# 12_-_CPU_-_POWER.net
KiCad netlist of a schematic drawn in Altium Designer
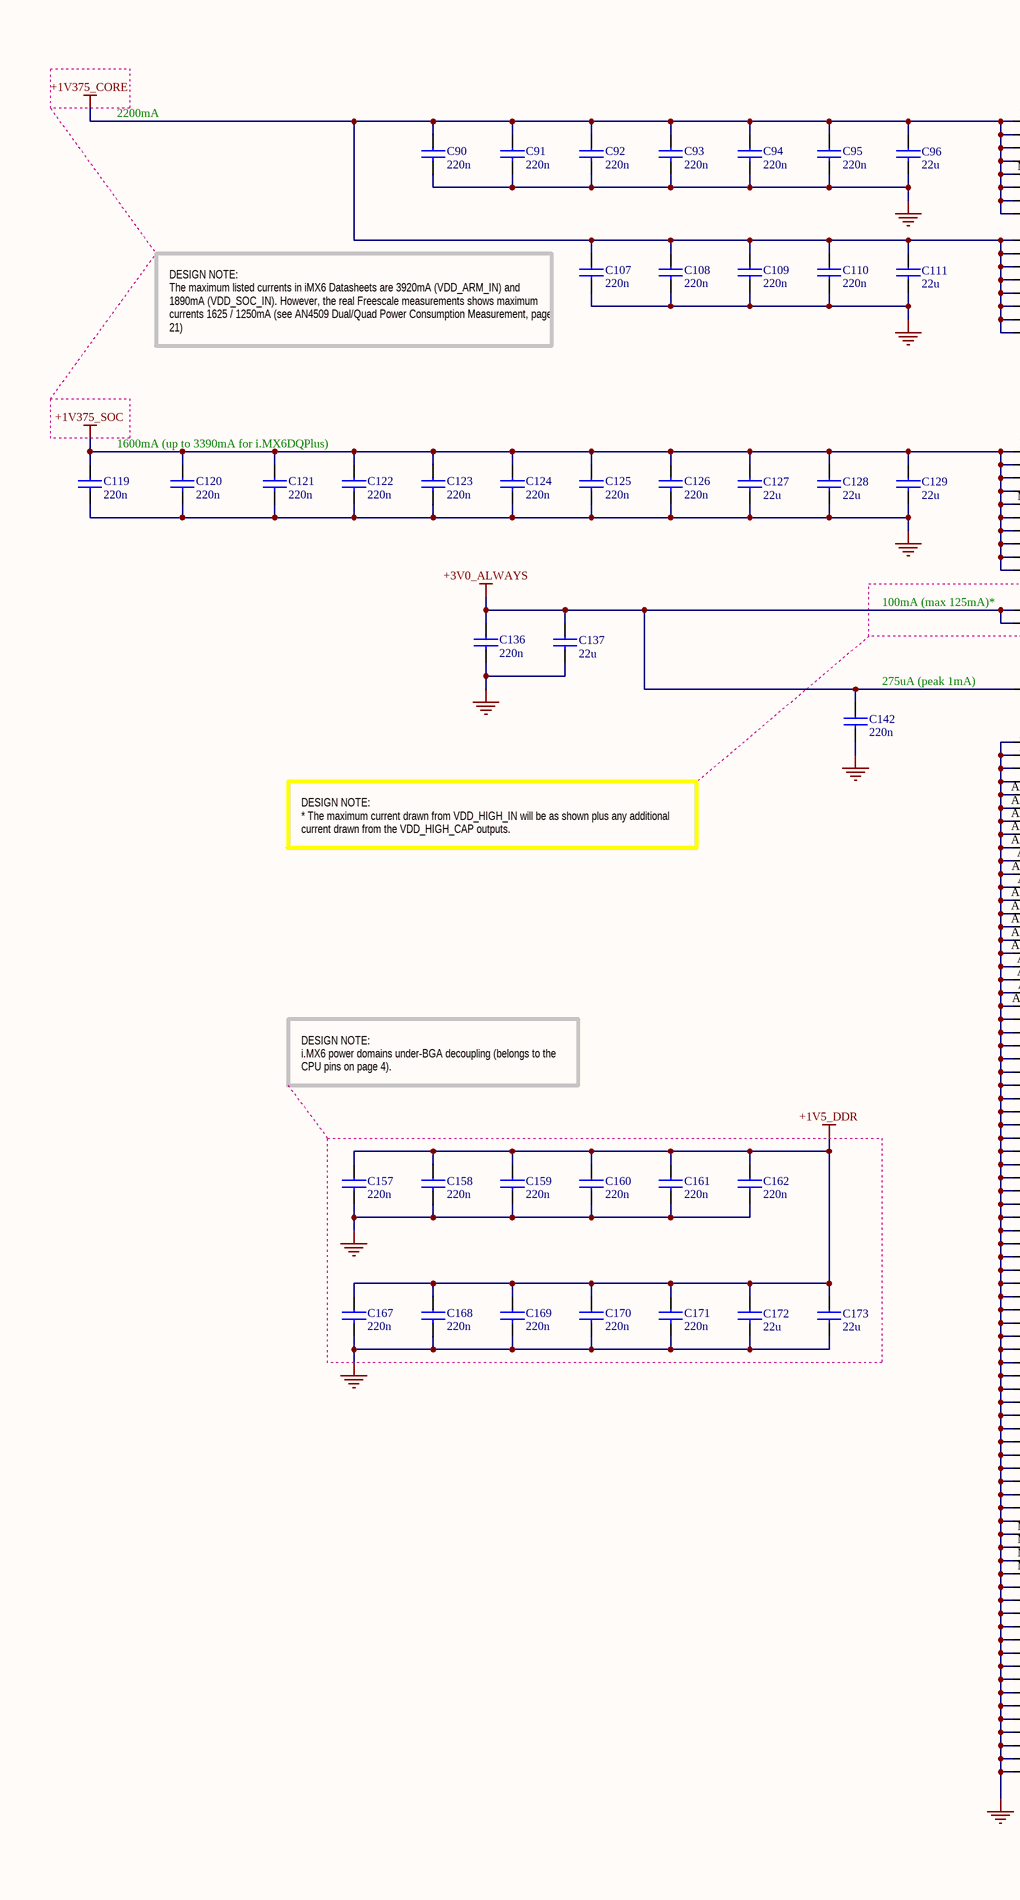
[diagram p0: [12] - CPU - POWER.SchDoc, left]
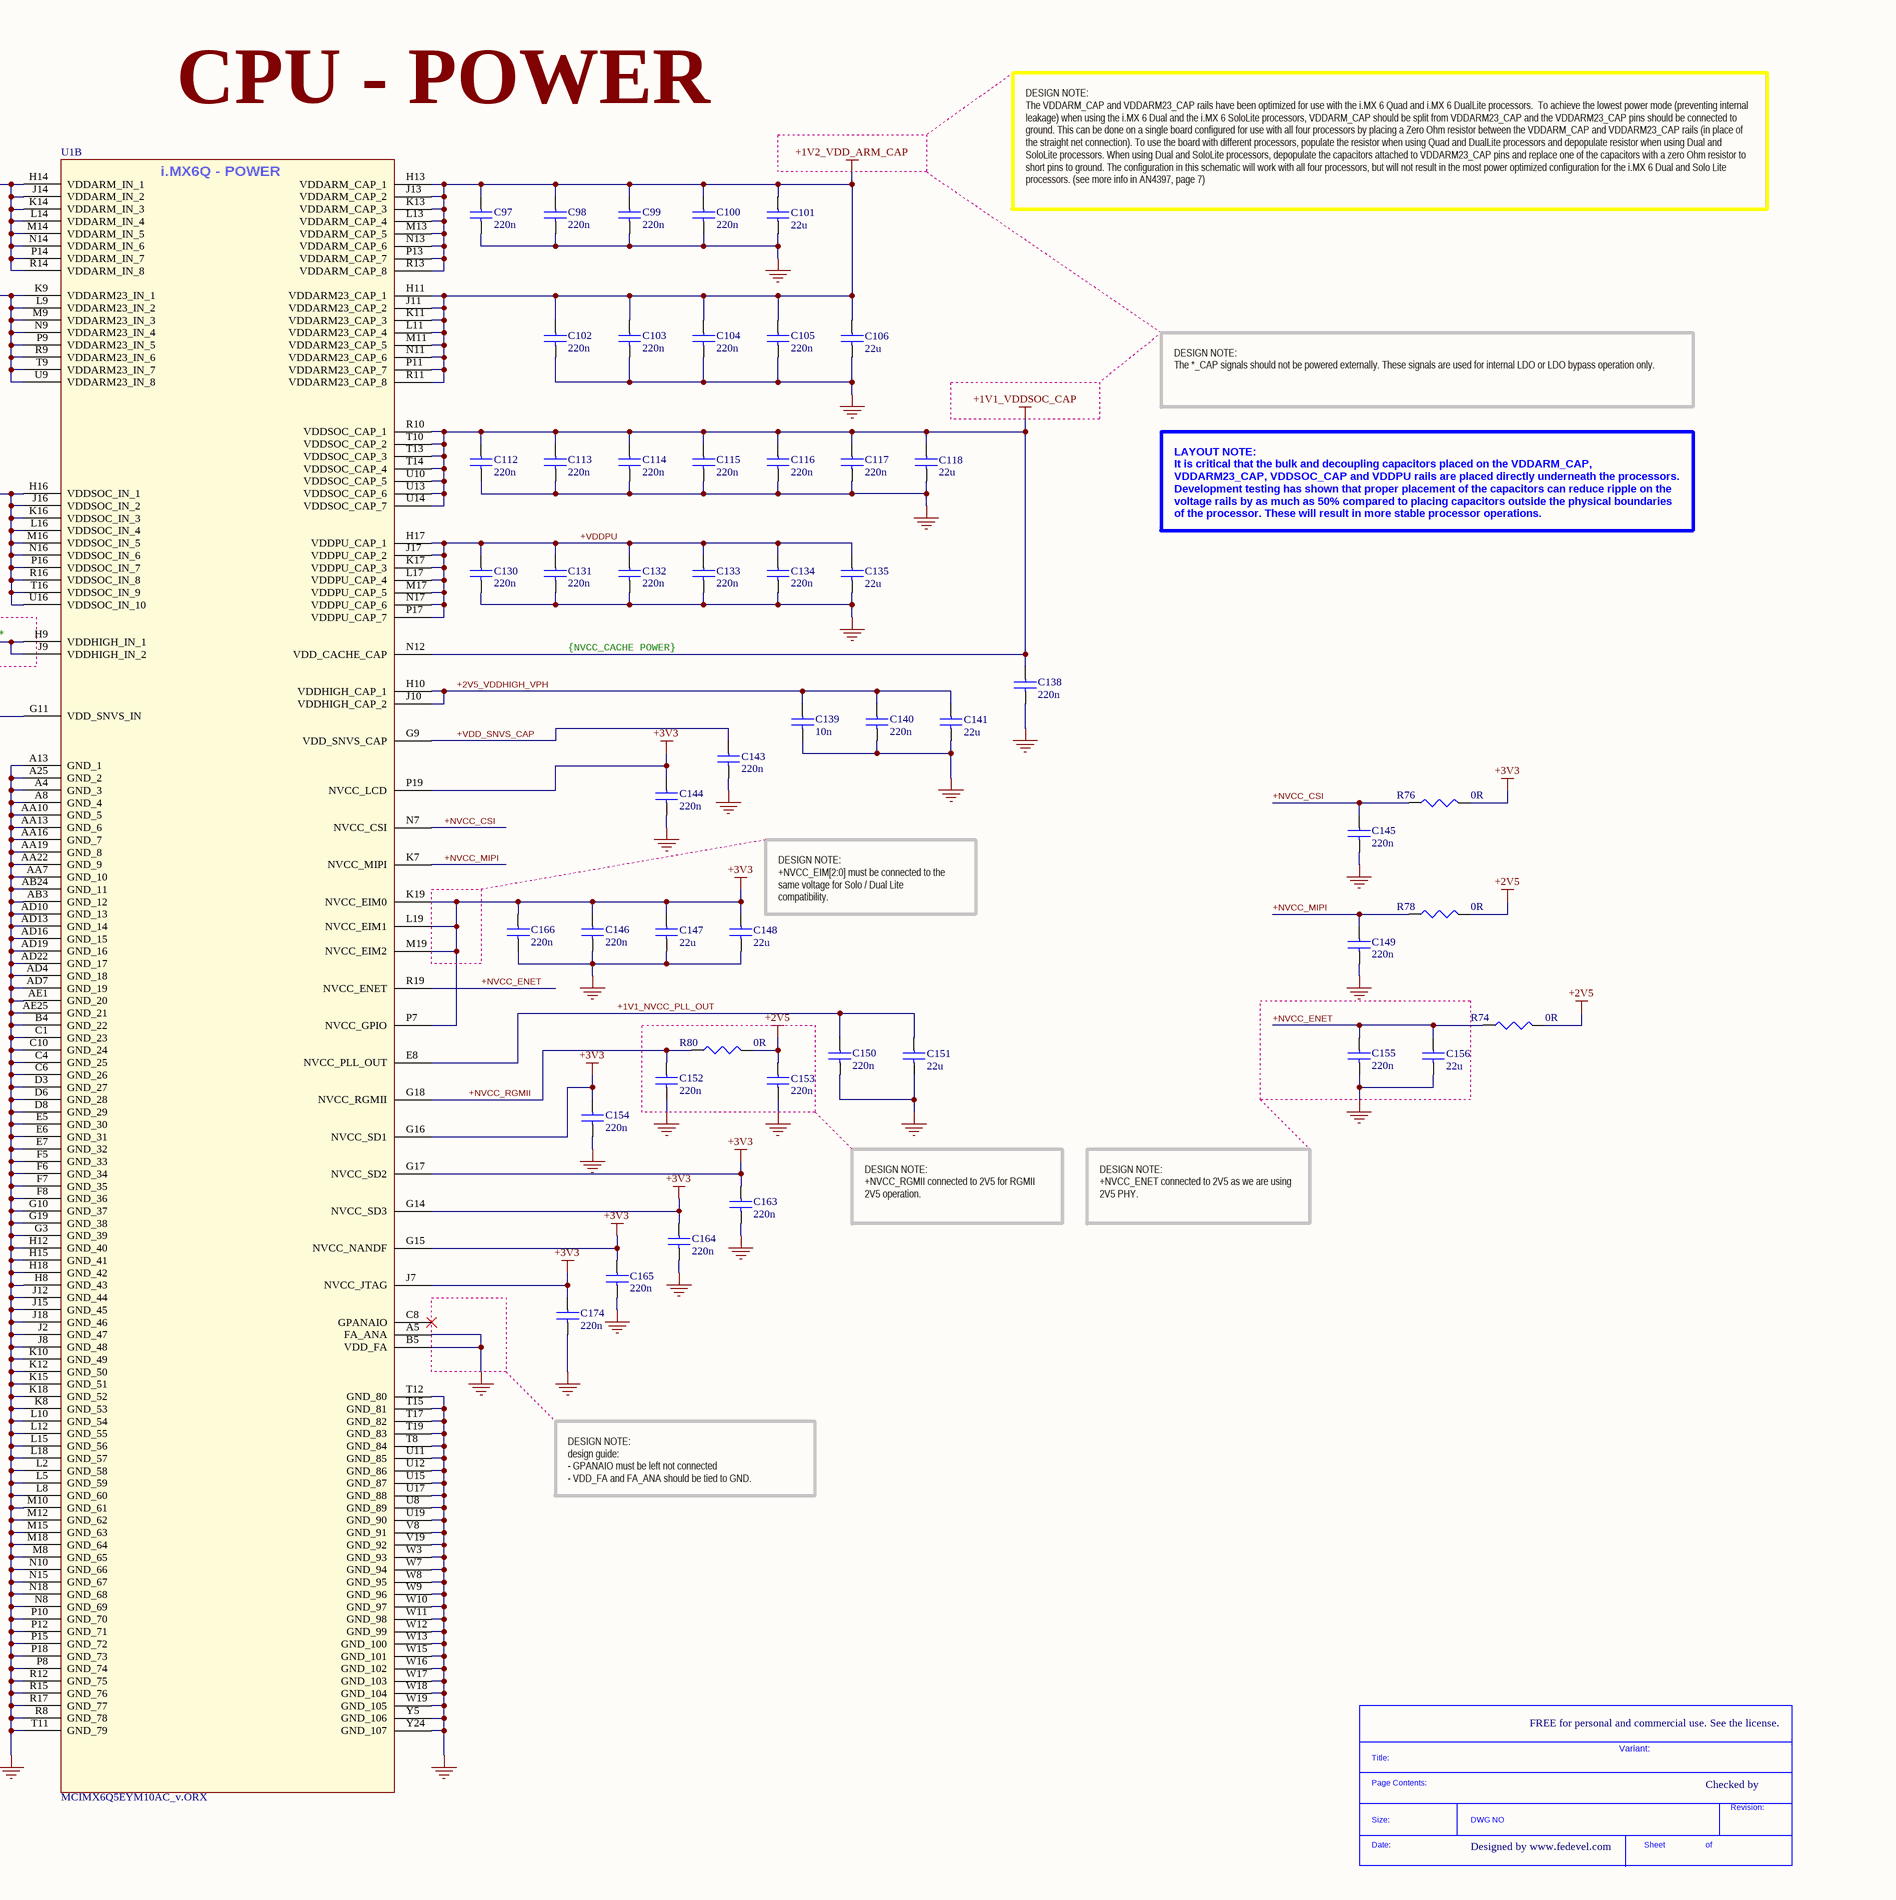
[diagram p1: [12] - CPU - POWER.SchDoc, right]

(export (version "E")
  (design (tool "Eeschema 10.0.6"))
  (components
    (comp (ref "C90")
      (value "220n")
      (footprint "C0201")
      (description "CAP CER 0.22UF 6.3V 20% X5R 0201")
      (fields
        (field (name "MANUFACTURER") "TDK Corporation")
        (field (name "MANUFACTURER PART NUMBER") "C0603X5R0J224M030BB")
        (field (name ".CHECKED PCB") "MM")
        (field (name ".CHECKED SCH") "MM")
        (field (name ".CREATOR") "MM")
      )
      (libsource (lib "Integrated_Library_FEDEVEL_0201") (part "C0603X5R0J224M030BB"))
    )
    (comp (ref "C91")
      (value "220n")
      (footprint "C0201")
      (description "CAP CER 0.22UF 6.3V 20% X5R 0201")
      (fields
        (field (name "MANUFACTURER") "TDK Corporation")
        (field (name "MANUFACTURER PART NUMBER") "C0603X5R0J224M030BB")
        (field (name ".CHECKED PCB") "MM")
        (field (name ".CHECKED SCH") "MM")
        (field (name ".CREATOR") "MM")
      )
      (libsource (lib "Integrated_Library_FEDEVEL_0201") (part "C0603X5R0J224M030BB"))
    )
    (comp (ref "C92")
      (value "220n")
      (footprint "C0201")
      (description "CAP CER 0.22UF 6.3V 20% X5R 0201")
      (fields
        (field (name "MANUFACTURER") "TDK Corporation")
        (field (name "MANUFACTURER PART NUMBER") "C0603X5R0J224M030BB")
        (field (name ".CHECKED PCB") "MM")
        (field (name ".CHECKED SCH") "MM")
        (field (name ".CREATOR") "MM")
      )
      (libsource (lib "Integrated_Library_FEDEVEL_0201") (part "C0603X5R0J224M030BB"))
    )
    (comp (ref "C93")
      (value "220n")
      (footprint "C0201")
      (description "CAP CER 0.22UF 6.3V 20% X5R 0201")
      (fields
        (field (name "MANUFACTURER") "TDK Corporation")
        (field (name "MANUFACTURER PART NUMBER") "C0603X5R0J224M030BB")
        (field (name ".CHECKED PCB") "MM")
        (field (name ".CHECKED SCH") "MM")
        (field (name ".CREATOR") "MM")
      )
      (libsource (lib "Integrated_Library_FEDEVEL_0201") (part "C0603X5R0J224M030BB"))
    )
    (comp (ref "C94")
      (value "220n")
      (footprint "C0201")
      (description "CAP CER 0.22UF 6.3V 20% X5R 0201")
      (fields
        (field (name "MANUFACTURER") "TDK Corporation")
        (field (name "MANUFACTURER PART NUMBER") "C0603X5R0J224M030BB")
        (field (name ".CHECKED PCB") "MM")
        (field (name ".CHECKED SCH") "MM")
        (field (name ".CREATOR") "MM")
      )
      (libsource (lib "Integrated_Library_FEDEVEL_0201") (part "C0603X5R0J224M030BB"))
    )
    (comp (ref "C95")
      (value "220n")
      (footprint "C0201")
      (description "CAP CER 0.22UF 6.3V 20% X5R 0201")
      (fields
        (field (name "MANUFACTURER") "TDK Corporation")
        (field (name "MANUFACTURER PART NUMBER") "C0603X5R0J224M030BB")
        (field (name ".CHECKED PCB") "MM")
        (field (name ".CHECKED SCH") "MM")
        (field (name ".CREATOR") "MM")
      )
      (libsource (lib "Integrated_Library_FEDEVEL_0201") (part "C0603X5R0J224M030BB"))
    )
    (comp (ref "C96")
      (value "22u")
      (footprint "C0603_small")
      (description "CAP CER 22UF 4V 20% X5R 0603")
      (fields
        (field (name "MANUFACTURER") "Murata Electronics North America")
        (field (name "MANUFACTURER PART NUMBER") "GRM188R60G226MEA0L")
        (field (name ".CHECKED PCB") "MM")
        (field (name ".CHECKED SCH") "RF, used by MM")
        (field (name ".CREATOR") "MM")
      )
      (libsource (lib "Integrated_Library_FEDEVEL_0201") (part "GRM188R60G226MEA0L_small"))
    )
    (comp (ref "C97")
      (value "220n")
      (footprint "C0201")
      (description "CAP CER 0.22UF 6.3V 20% X5R 0201")
      (fields
        (field (name "MANUFACTURER") "TDK Corporation")
        (field (name "MANUFACTURER PART NUMBER") "C0603X5R0J224M030BB")
        (field (name ".CHECKED PCB") "MM")
        (field (name ".CHECKED SCH") "MM")
        (field (name ".CREATOR") "MM")
      )
      (libsource (lib "Integrated_Library_FEDEVEL_0201") (part "C0603X5R0J224M030BB"))
    )
    (comp (ref "C98")
      (value "220n")
      (footprint "C0201")
      (description "CAP CER 0.22UF 6.3V 20% X5R 0201")
      (fields
        (field (name "MANUFACTURER") "TDK Corporation")
        (field (name "MANUFACTURER PART NUMBER") "C0603X5R0J224M030BB")
        (field (name ".CHECKED PCB") "MM")
        (field (name ".CHECKED SCH") "MM")
        (field (name ".CREATOR") "MM")
      )
      (libsource (lib "Integrated_Library_FEDEVEL_0201") (part "C0603X5R0J224M030BB"))
    )
    (comp (ref "C99")
      (value "220n")
      (footprint "C0201")
      (description "CAP CER 0.22UF 6.3V 20% X5R 0201")
      (fields
        (field (name "MANUFACTURER") "TDK Corporation")
        (field (name "MANUFACTURER PART NUMBER") "C0603X5R0J224M030BB")
        (field (name ".CHECKED PCB") "MM")
        (field (name ".CHECKED SCH") "MM")
        (field (name ".CREATOR") "MM")
      )
      (libsource (lib "Integrated_Library_FEDEVEL_0201") (part "C0603X5R0J224M030BB"))
    )
    (comp (ref "C100")
      (value "220n")
      (footprint "C0201")
      (description "CAP CER 0.22UF 6.3V 20% X5R 0201")
      (fields
        (field (name "MANUFACTURER") "TDK Corporation")
        (field (name "MANUFACTURER PART NUMBER") "C0603X5R0J224M030BB")
        (field (name ".CHECKED PCB") "MM")
        (field (name ".CHECKED SCH") "MM")
        (field (name ".CREATOR") "MM")
      )
      (libsource (lib "Integrated_Library_FEDEVEL_0201") (part "C0603X5R0J224M030BB"))
    )
    (comp (ref "C101")
      (value "22u")
      (footprint "C0603_small")
      (description "CAP CER 22UF 4V 20% X5R 0603")
      (fields
        (field (name "MANUFACTURER") "Murata Electronics North America")
        (field (name "MANUFACTURER PART NUMBER") "GRM188R60G226MEA0L")
        (field (name ".CHECKED PCB") "MM")
        (field (name ".CHECKED SCH") "RF, used by MM")
        (field (name ".CREATOR") "MM")
      )
      (libsource (lib "Integrated_Library_FEDEVEL_0201") (part "GRM188R60G226MEA0L_small"))
    )
    (comp (ref "C102")
      (value "220n")
      (footprint "C0201")
      (description "CAP CER 0.22UF 6.3V 20% X5R 0201")
      (fields
        (field (name "MANUFACTURER") "TDK Corporation")
        (field (name "MANUFACTURER PART NUMBER") "C0603X5R0J224M030BB")
        (field (name ".CHECKED PCB") "MM")
        (field (name ".CHECKED SCH") "MM")
        (field (name ".CREATOR") "MM")
      )
      (libsource (lib "Integrated_Library_FEDEVEL_0201") (part "C0603X5R0J224M030BB"))
    )
    (comp (ref "C103")
      (value "220n")
      (footprint "C0201")
      (description "CAP CER 0.22UF 6.3V 20% X5R 0201")
      (fields
        (field (name "MANUFACTURER") "TDK Corporation")
        (field (name "MANUFACTURER PART NUMBER") "C0603X5R0J224M030BB")
        (field (name ".CHECKED PCB") "MM")
        (field (name ".CHECKED SCH") "MM")
        (field (name ".CREATOR") "MM")
      )
      (libsource (lib "Integrated_Library_FEDEVEL_0201") (part "C0603X5R0J224M030BB"))
    )
    (comp (ref "C104")
      (value "220n")
      (footprint "C0201")
      (description "CAP CER 0.22UF 6.3V 20% X5R 0201")
      (fields
        (field (name "MANUFACTURER") "TDK Corporation")
        (field (name "MANUFACTURER PART NUMBER") "C0603X5R0J224M030BB")
        (field (name ".CHECKED PCB") "MM")
        (field (name ".CHECKED SCH") "MM")
        (field (name ".CREATOR") "MM")
      )
      (libsource (lib "Integrated_Library_FEDEVEL_0201") (part "C0603X5R0J224M030BB"))
    )
    (comp (ref "C105")
      (value "220n")
      (footprint "C0201")
      (description "CAP CER 0.22UF 6.3V 20% X5R 0201")
      (fields
        (field (name "MANUFACTURER") "TDK Corporation")
        (field (name "MANUFACTURER PART NUMBER") "C0603X5R0J224M030BB")
        (field (name ".CHECKED PCB") "MM")
        (field (name ".CHECKED SCH") "MM")
        (field (name ".CREATOR") "MM")
      )
      (libsource (lib "Integrated_Library_FEDEVEL_0201") (part "C0603X5R0J224M030BB"))
    )
    (comp (ref "C106")
      (value "22u")
      (footprint "C0603_small")
      (description "CAP CER 22UF 4V 20% X5R 0603")
      (fields
        (field (name "MANUFACTURER") "Murata Electronics North America")
        (field (name "MANUFACTURER PART NUMBER") "GRM188R60G226MEA0L")
        (field (name ".CHECKED PCB") "MM")
        (field (name ".CHECKED SCH") "RF, used by MM")
        (field (name ".CREATOR") "MM")
      )
      (libsource (lib "Integrated_Library_FEDEVEL_0201") (part "GRM188R60G226MEA0L_small"))
    )
    (comp (ref "C107")
      (value "220n")
      (footprint "C0201")
      (description "CAP CER 0.22UF 6.3V 20% X5R 0201")
      (fields
        (field (name "MANUFACTURER") "TDK Corporation")
        (field (name "MANUFACTURER PART NUMBER") "C0603X5R0J224M030BB")
        (field (name ".CHECKED PCB") "MM")
        (field (name ".CHECKED SCH") "MM")
        (field (name ".CREATOR") "MM")
      )
      (libsource (lib "Integrated_Library_FEDEVEL_0201") (part "C0603X5R0J224M030BB"))
    )
    (comp (ref "C108")
      (value "220n")
      (footprint "C0201")
      (description "CAP CER 0.22UF 6.3V 20% X5R 0201")
      (fields
        (field (name "MANUFACTURER") "TDK Corporation")
        (field (name "MANUFACTURER PART NUMBER") "C0603X5R0J224M030BB")
        (field (name ".CHECKED PCB") "MM")
        (field (name ".CHECKED SCH") "MM")
        (field (name ".CREATOR") "MM")
      )
      (libsource (lib "Integrated_Library_FEDEVEL_0201") (part "C0603X5R0J224M030BB"))
    )
    (comp (ref "C109")
      (value "220n")
      (footprint "C0201")
      (description "CAP CER 0.22UF 6.3V 20% X5R 0201")
      (fields
        (field (name "MANUFACTURER") "TDK Corporation")
        (field (name "MANUFACTURER PART NUMBER") "C0603X5R0J224M030BB")
        (field (name ".CHECKED PCB") "MM")
        (field (name ".CHECKED SCH") "MM")
        (field (name ".CREATOR") "MM")
      )
      (libsource (lib "Integrated_Library_FEDEVEL_0201") (part "C0603X5R0J224M030BB"))
    )
    (comp (ref "C110")
      (value "220n")
      (footprint "C0201")
      (description "CAP CER 0.22UF 6.3V 20% X5R 0201")
      (fields
        (field (name "MANUFACTURER") "TDK Corporation")
        (field (name "MANUFACTURER PART NUMBER") "C0603X5R0J224M030BB")
        (field (name ".CHECKED PCB") "MM")
        (field (name ".CHECKED SCH") "MM")
        (field (name ".CREATOR") "MM")
      )
      (libsource (lib "Integrated_Library_FEDEVEL_0201") (part "C0603X5R0J224M030BB"))
    )
    (comp (ref "C111")
      (value "22u")
      (footprint "C0603_small")
      (description "CAP CER 22UF 4V 20% X5R 0603")
      (fields
        (field (name "MANUFACTURER") "Murata Electronics North America")
        (field (name "MANUFACTURER PART NUMBER") "GRM188R60G226MEA0L")
        (field (name ".CHECKED PCB") "MM")
        (field (name ".CHECKED SCH") "RF, used by MM")
        (field (name ".CREATOR") "MM")
      )
      (libsource (lib "Integrated_Library_FEDEVEL_0201") (part "GRM188R60G226MEA0L_small"))
    )
    (comp (ref "C112")
      (value "220n")
      (footprint "C0201")
      (description "CAP CER 0.22UF 6.3V 20% X5R 0201")
      (fields
        (field (name "MANUFACTURER") "TDK Corporation")
        (field (name "MANUFACTURER PART NUMBER") "C0603X5R0J224M030BB")
        (field (name ".CHECKED PCB") "MM")
        (field (name ".CHECKED SCH") "MM")
        (field (name ".CREATOR") "MM")
      )
      (libsource (lib "Integrated_Library_FEDEVEL_0201") (part "C0603X5R0J224M030BB"))
    )
    (comp (ref "C113")
      (value "220n")
      (footprint "C0201")
      (description "CAP CER 0.22UF 6.3V 20% X5R 0201")
      (fields
        (field (name "MANUFACTURER") "TDK Corporation")
        (field (name "MANUFACTURER PART NUMBER") "C0603X5R0J224M030BB")
        (field (name ".CHECKED PCB") "MM")
        (field (name ".CHECKED SCH") "MM")
        (field (name ".CREATOR") "MM")
      )
      (libsource (lib "Integrated_Library_FEDEVEL_0201") (part "C0603X5R0J224M030BB"))
    )
    (comp (ref "C114")
      (value "220n")
      (footprint "C0201")
      (description "CAP CER 0.22UF 6.3V 20% X5R 0201")
      (fields
        (field (name "MANUFACTURER") "TDK Corporation")
        (field (name "MANUFACTURER PART NUMBER") "C0603X5R0J224M030BB")
        (field (name ".CHECKED PCB") "MM")
        (field (name ".CHECKED SCH") "MM")
        (field (name ".CREATOR") "MM")
      )
      (libsource (lib "Integrated_Library_FEDEVEL_0201") (part "C0603X5R0J224M030BB"))
    )
    (comp (ref "C115")
      (value "220n")
      (footprint "C0201")
      (description "CAP CER 0.22UF 6.3V 20% X5R 0201")
      (fields
        (field (name "MANUFACTURER") "TDK Corporation")
        (field (name "MANUFACTURER PART NUMBER") "C0603X5R0J224M030BB")
        (field (name ".CHECKED PCB") "MM")
        (field (name ".CHECKED SCH") "MM")
        (field (name ".CREATOR") "MM")
      )
      (libsource (lib "Integrated_Library_FEDEVEL_0201") (part "C0603X5R0J224M030BB"))
    )
    (comp (ref "C116")
      (value "220n")
      (footprint "C0201")
      (description "CAP CER 0.22UF 6.3V 20% X5R 0201")
      (fields
        (field (name "MANUFACTURER") "TDK Corporation")
        (field (name "MANUFACTURER PART NUMBER") "C0603X5R0J224M030BB")
        (field (name ".CHECKED PCB") "MM")
        (field (name ".CHECKED SCH") "MM")
        (field (name ".CREATOR") "MM")
      )
      (libsource (lib "Integrated_Library_FEDEVEL_0201") (part "C0603X5R0J224M030BB"))
    )
    (comp (ref "C117")
      (value "220n")
      (footprint "C0201")
      (description "CAP CER 0.22UF 6.3V 20% X5R 0201")
      (fields
        (field (name "MANUFACTURER") "TDK Corporation")
        (field (name "MANUFACTURER PART NUMBER") "C0603X5R0J224M030BB")
        (field (name ".CHECKED PCB") "MM")
        (field (name ".CHECKED SCH") "MM")
        (field (name ".CREATOR") "MM")
      )
      (libsource (lib "Integrated_Library_FEDEVEL_0201") (part "C0603X5R0J224M030BB"))
    )
    (comp (ref "C118")
      (value "22u")
      (footprint "C0603_small")
      (description "CAP CER 22UF 4V 20% X5R 0603")
      (fields
        (field (name "MANUFACTURER") "Murata Electronics North America")
        (field (name "MANUFACTURER PART NUMBER") "GRM188R60G226MEA0L")
        (field (name ".CHECKED PCB") "MM")
        (field (name ".CHECKED SCH") "RF, used by MM")
        (field (name ".CREATOR") "MM")
      )
      (libsource (lib "Integrated_Library_FEDEVEL_0201") (part "GRM188R60G226MEA0L_small"))
    )
    (comp (ref "C119")
      (value "220n")
      (footprint "C0201")
      (description "CAP CER 0.22UF 6.3V 20% X5R 0201")
      (fields
        (field (name "MANUFACTURER") "TDK Corporation")
        (field (name "MANUFACTURER PART NUMBER") "C0603X5R0J224M030BB")
        (field (name ".CHECKED PCB") "MM")
        (field (name ".CHECKED SCH") "MM")
        (field (name ".CREATOR") "MM")
      )
      (libsource (lib "Integrated_Library_FEDEVEL_0201") (part "C0603X5R0J224M030BB"))
    )
    (comp (ref "C120")
      (value "220n")
      (footprint "C0201")
      (description "CAP CER 0.22UF 6.3V 20% X5R 0201")
      (fields
        (field (name "MANUFACTURER") "TDK Corporation")
        (field (name "MANUFACTURER PART NUMBER") "C0603X5R0J224M030BB")
        (field (name ".CHECKED PCB") "MM")
        (field (name ".CHECKED SCH") "MM")
        (field (name ".CREATOR") "MM")
      )
      (libsource (lib "Integrated_Library_FEDEVEL_0201") (part "C0603X5R0J224M030BB"))
    )
    (comp (ref "C121")
      (value "220n")
      (footprint "C0201")
      (description "CAP CER 0.22UF 6.3V 20% X5R 0201")
      (fields
        (field (name "MANUFACTURER") "TDK Corporation")
        (field (name "MANUFACTURER PART NUMBER") "C0603X5R0J224M030BB")
        (field (name ".CHECKED PCB") "MM")
        (field (name ".CHECKED SCH") "MM")
        (field (name ".CREATOR") "MM")
      )
      (libsource (lib "Integrated_Library_FEDEVEL_0201") (part "C0603X5R0J224M030BB"))
    )
    (comp (ref "C122")
      (value "220n")
      (footprint "C0201")
      (description "CAP CER 0.22UF 6.3V 20% X5R 0201")
      (fields
        (field (name "MANUFACTURER") "TDK Corporation")
        (field (name "MANUFACTURER PART NUMBER") "C0603X5R0J224M030BB")
        (field (name ".CHECKED PCB") "MM")
        (field (name ".CHECKED SCH") "MM")
        (field (name ".CREATOR") "MM")
      )
      (libsource (lib "Integrated_Library_FEDEVEL_0201") (part "C0603X5R0J224M030BB"))
    )
    (comp (ref "C123")
      (value "220n")
      (footprint "C0201")
      (description "CAP CER 0.22UF 6.3V 20% X5R 0201")
      (fields
        (field (name "MANUFACTURER") "TDK Corporation")
        (field (name "MANUFACTURER PART NUMBER") "C0603X5R0J224M030BB")
        (field (name ".CHECKED PCB") "MM")
        (field (name ".CHECKED SCH") "MM")
        (field (name ".CREATOR") "MM")
      )
      (libsource (lib "Integrated_Library_FEDEVEL_0201") (part "C0603X5R0J224M030BB"))
    )
    (comp (ref "C124")
      (value "220n")
      (footprint "C0201")
      (description "CAP CER 0.22UF 6.3V 20% X5R 0201")
      (fields
        (field (name "MANUFACTURER") "TDK Corporation")
        (field (name "MANUFACTURER PART NUMBER") "C0603X5R0J224M030BB")
        (field (name ".CHECKED PCB") "MM")
        (field (name ".CHECKED SCH") "MM")
        (field (name ".CREATOR") "MM")
      )
      (libsource (lib "Integrated_Library_FEDEVEL_0201") (part "C0603X5R0J224M030BB"))
    )
    (comp (ref "C125")
      (value "220n")
      (footprint "C0201")
      (description "CAP CER 0.22UF 6.3V 20% X5R 0201")
      (fields
        (field (name "MANUFACTURER") "TDK Corporation")
        (field (name "MANUFACTURER PART NUMBER") "C0603X5R0J224M030BB")
        (field (name ".CHECKED PCB") "MM")
        (field (name ".CHECKED SCH") "MM")
        (field (name ".CREATOR") "MM")
      )
      (libsource (lib "Integrated_Library_FEDEVEL_0201") (part "C0603X5R0J224M030BB"))
    )
    (comp (ref "C126")
      (value "220n")
      (footprint "C0201")
      (description "CAP CER 0.22UF 6.3V 20% X5R 0201")
      (fields
        (field (name "MANUFACTURER") "TDK Corporation")
        (field (name "MANUFACTURER PART NUMBER") "C0603X5R0J224M030BB")
        (field (name ".CHECKED PCB") "MM")
        (field (name ".CHECKED SCH") "MM")
        (field (name ".CREATOR") "MM")
      )
      (libsource (lib "Integrated_Library_FEDEVEL_0201") (part "C0603X5R0J224M030BB"))
    )
    (comp (ref "C127")
      (value "22u")
      (footprint "C0603_small")
      (description "CAP CER 22UF 4V 20% X5R 0603")
      (fields
        (field (name "MANUFACTURER") "Murata Electronics North America")
        (field (name "MANUFACTURER PART NUMBER") "GRM188R60G226MEA0L")
        (field (name ".CHECKED PCB") "MM")
        (field (name ".CHECKED SCH") "RF, used by MM")
        (field (name ".CREATOR") "MM")
      )
      (libsource (lib "Integrated_Library_FEDEVEL_0201") (part "GRM188R60G226MEA0L_small"))
    )
    (comp (ref "C128")
      (value "22u")
      (footprint "C0603_small")
      (description "CAP CER 22UF 4V 20% X5R 0603")
      (fields
        (field (name "MANUFACTURER") "Murata Electronics North America")
        (field (name "MANUFACTURER PART NUMBER") "GRM188R60G226MEA0L")
        (field (name ".CHECKED PCB") "MM")
        (field (name ".CHECKED SCH") "RF, used by MM")
        (field (name ".CREATOR") "MM")
      )
      (libsource (lib "Integrated_Library_FEDEVEL_0201") (part "GRM188R60G226MEA0L_small"))
    )
    (comp (ref "C129")
      (value "22u")
      (footprint "C0603_small")
      (description "CAP CER 22UF 4V 20% X5R 0603")
      (fields
        (field (name "MANUFACTURER") "Murata Electronics North America")
        (field (name "MANUFACTURER PART NUMBER") "GRM188R60G226MEA0L")
        (field (name ".CHECKED PCB") "MM")
        (field (name ".CHECKED SCH") "RF, used by MM")
        (field (name ".CREATOR") "MM")
      )
      (libsource (lib "Integrated_Library_FEDEVEL_0201") (part "GRM188R60G226MEA0L_small"))
    )
    (comp (ref "C130")
      (value "220n")
      (footprint "C0201")
      (description "CAP CER 0.22UF 6.3V 20% X5R 0201")
      (fields
        (field (name "MANUFACTURER") "TDK Corporation")
        (field (name "MANUFACTURER PART NUMBER") "C0603X5R0J224M030BB")
        (field (name ".CHECKED PCB") "MM")
        (field (name ".CHECKED SCH") "MM")
        (field (name ".CREATOR") "MM")
      )
      (libsource (lib "Integrated_Library_FEDEVEL_0201") (part "C0603X5R0J224M030BB"))
    )
    (comp (ref "C131")
      (value "220n")
      (footprint "C0201")
      (description "CAP CER 0.22UF 6.3V 20% X5R 0201")
      (fields
        (field (name "MANUFACTURER") "TDK Corporation")
        (field (name "MANUFACTURER PART NUMBER") "C0603X5R0J224M030BB")
        (field (name ".CHECKED PCB") "MM")
        (field (name ".CHECKED SCH") "MM")
        (field (name ".CREATOR") "MM")
      )
      (libsource (lib "Integrated_Library_FEDEVEL_0201") (part "C0603X5R0J224M030BB"))
    )
    (comp (ref "C132")
      (value "220n")
      (footprint "C0201")
      (description "CAP CER 0.22UF 6.3V 20% X5R 0201")
      (fields
        (field (name "MANUFACTURER") "TDK Corporation")
        (field (name "MANUFACTURER PART NUMBER") "C0603X5R0J224M030BB")
        (field (name ".CHECKED PCB") "MM")
        (field (name ".CHECKED SCH") "MM")
        (field (name ".CREATOR") "MM")
      )
      (libsource (lib "Integrated_Library_FEDEVEL_0201") (part "C0603X5R0J224M030BB"))
    )
    (comp (ref "C133")
      (value "220n")
      (footprint "C0201")
      (description "CAP CER 0.22UF 6.3V 20% X5R 0201")
      (fields
        (field (name "MANUFACTURER") "TDK Corporation")
        (field (name "MANUFACTURER PART NUMBER") "C0603X5R0J224M030BB")
        (field (name ".CHECKED PCB") "MM")
        (field (name ".CHECKED SCH") "MM")
        (field (name ".CREATOR") "MM")
      )
      (libsource (lib "Integrated_Library_FEDEVEL_0201") (part "C0603X5R0J224M030BB"))
    )
    (comp (ref "C134")
      (value "220n")
      (footprint "C0201")
      (description "CAP CER 0.22UF 6.3V 20% X5R 0201")
      (fields
        (field (name "MANUFACTURER") "TDK Corporation")
        (field (name "MANUFACTURER PART NUMBER") "C0603X5R0J224M030BB")
        (field (name ".CHECKED PCB") "MM")
        (field (name ".CHECKED SCH") "MM")
        (field (name ".CREATOR") "MM")
      )
      (libsource (lib "Integrated_Library_FEDEVEL_0201") (part "C0603X5R0J224M030BB"))
    )
    (comp (ref "C135")
      (value "22u")
      (footprint "C0603_small")
      (description "CAP CER 22UF 4V 20% X5R 0603")
      (fields
        (field (name "MANUFACTURER") "Murata Electronics North America")
        (field (name "MANUFACTURER PART NUMBER") "GRM188R60G226MEA0L")
        (field (name ".CHECKED PCB") "MM")
        (field (name ".CHECKED SCH") "RF, used by MM")
        (field (name ".CREATOR") "MM")
      )
      (libsource (lib "Integrated_Library_FEDEVEL_0201") (part "GRM188R60G226MEA0L_small"))
    )
    (comp (ref "C136")
      (value "220n")
      (footprint "C0201")
      (description "CAP CER 0.22UF 6.3V 20% X5R 0201")
      (fields
        (field (name "MANUFACTURER") "TDK Corporation")
        (field (name "MANUFACTURER PART NUMBER") "C0603X5R0J224M030BB")
        (field (name ".CHECKED PCB") "MM")
        (field (name ".CHECKED SCH") "MM")
        (field (name ".CREATOR") "MM")
      )
      (libsource (lib "Integrated_Library_FEDEVEL_0201") (part "C0603X5R0J224M030BB"))
    )
    (comp (ref "C137")
      (value "22u")
      (footprint "C0603")
      (description "CAP CER 22UF 6.3V 20% X5R 0603")
      (fields
        (field (name "MANUFACTURER") "TDK Corporation")
        (field (name "MANUFACTURER PART NUMBER") "C1608X5R0J226M080AC")
        (field (name ".CREATOR") "MM")
        (field (name ".CHECKED PCB") "MM")
        (field (name ".CHECKED SCH") "MM")
      )
      (libsource (lib "Integrated_Library_FEDEVEL_APR_2015") (part "C1608X5R0J226M080AC"))
    )
    (comp (ref "C138")
      (value "220n")
      (footprint "C0201")
      (description "CAP CER 0.22UF 6.3V 20% X5R 0201")
      (fields
        (field (name "MANUFACTURER") "TDK Corporation")
        (field (name "MANUFACTURER PART NUMBER") "C0603X5R0J224M030BB")
        (field (name ".CHECKED PCB") "MM")
        (field (name ".CHECKED SCH") "MM")
        (field (name ".CREATOR") "MM")
      )
      (libsource (lib "Integrated_Library_FEDEVEL_0201") (part "C0603X5R0J224M030BB"))
    )
    (comp (ref "C139")
      (value "10n")
      (footprint "C0201")
      (description "CAP CER .01UF 16V 10% X5R 0201")
      (fields
        (field (name "MANUFACTURER") "TDK Corporation")
        (field (name "MANUFACTURER PART NUMBER") "C0603X5R1C103K030BA")
        (field (name ".CREATOR") "MM")
        (field (name ".CHECKED PCB") "MM")
        (field (name ".CHECKED SCH") "MM")
      )
      (libsource (lib "Integrated_Library_FEDEVEL_0201") (part "C0603X5R1C103K030BA"))
    )
    (comp (ref "C140")
      (value "220n")
      (footprint "C0201")
      (description "CAP CER 0.22UF 6.3V 20% X5R 0201")
      (fields
        (field (name "MANUFACTURER") "TDK Corporation")
        (field (name "MANUFACTURER PART NUMBER") "C0603X5R0J224M030BB")
        (field (name ".CHECKED PCB") "MM")
        (field (name ".CHECKED SCH") "MM")
        (field (name ".CREATOR") "MM")
      )
      (libsource (lib "Integrated_Library_FEDEVEL_0201") (part "C0603X5R0J224M030BB"))
    )
    (comp (ref "C141")
      (value "22u")
      (footprint "C0603")
      (description "CAP CER 22UF 6.3V 20% X5R 0603")
      (fields
        (field (name "MANUFACTURER") "TDK Corporation")
        (field (name "MANUFACTURER PART NUMBER") "C1608X5R0J226M080AC")
        (field (name ".CREATOR") "MM")
        (field (name ".CHECKED PCB") "MM")
        (field (name ".CHECKED SCH") "MM")
      )
      (libsource (lib "Integrated_Library_FEDEVEL_APR_2015") (part "C1608X5R0J226M080AC"))
    )
    (comp (ref "C142")
      (value "220n")
      (footprint "C0201")
      (description "CAP CER 0.22UF 6.3V 20% X5R 0201")
      (fields
        (field (name "MANUFACTURER") "TDK Corporation")
        (field (name "MANUFACTURER PART NUMBER") "C0603X5R0J224M030BB")
        (field (name ".CHECKED PCB") "MM")
        (field (name ".CHECKED SCH") "MM")
        (field (name ".CREATOR") "MM")
      )
      (libsource (lib "Integrated_Library_FEDEVEL_0201") (part "C0603X5R0J224M030BB"))
    )
    (comp (ref "C143")
      (value "220n")
      (footprint "C0201")
      (description "CAP CER 0.22UF 6.3V 20% X5R 0201")
      (fields
        (field (name "MANUFACTURER") "TDK Corporation")
        (field (name "MANUFACTURER PART NUMBER") "C0603X5R0J224M030BB")
        (field (name ".CHECKED PCB") "MM")
        (field (name ".CHECKED SCH") "MM")
        (field (name ".CREATOR") "MM")
      )
      (libsource (lib "Integrated_Library_FEDEVEL_0201") (part "C0603X5R0J224M030BB"))
    )
    (comp (ref "C144")
      (value "220n")
      (footprint "C0201")
      (description "CAP CER 0.22UF 6.3V 20% X5R 0201")
      (fields
        (field (name "MANUFACTURER") "TDK Corporation")
        (field (name "MANUFACTURER PART NUMBER") "C0603X5R0J224M030BB")
        (field (name ".CHECKED PCB") "MM")
        (field (name ".CHECKED SCH") "MM")
        (field (name ".CREATOR") "MM")
      )
      (libsource (lib "Integrated_Library_FEDEVEL_0201") (part "C0603X5R0J224M030BB"))
    )
    (comp (ref "C145")
      (value "220n")
      (footprint "C0201")
      (description "CAP CER 0.22UF 6.3V 20% X5R 0201")
      (fields
        (field (name "MANUFACTURER") "TDK Corporation")
        (field (name "MANUFACTURER PART NUMBER") "C0603X5R0J224M030BB")
        (field (name ".CHECKED PCB") "MM")
        (field (name ".CHECKED SCH") "MM")
        (field (name ".CREATOR") "MM")
      )
      (libsource (lib "Integrated_Library_FEDEVEL_0201") (part "C0603X5R0J224M030BB"))
    )
    (comp (ref "C146")
      (value "220n")
      (footprint "C0201")
      (description "CAP CER 0.22UF 6.3V 20% X5R 0201")
      (fields
        (field (name "MANUFACTURER") "TDK Corporation")
        (field (name "MANUFACTURER PART NUMBER") "C0603X5R0J224M030BB")
        (field (name ".CHECKED PCB") "MM")
        (field (name ".CHECKED SCH") "MM")
        (field (name ".CREATOR") "MM")
      )
      (libsource (lib "Integrated_Library_FEDEVEL_0201") (part "C0603X5R0J224M030BB"))
    )
    (comp (ref "C147")
      (value "22u")
      (footprint "C0603")
      (description "CAP CER 22UF 6.3V 20% X5R 0603")
      (fields
        (field (name "MANUFACTURER") "TDK Corporation")
        (field (name "MANUFACTURER PART NUMBER") "C1608X5R0J226M080AC")
        (field (name ".CREATOR") "MM")
        (field (name ".CHECKED PCB") "MM")
        (field (name ".CHECKED SCH") "MM")
      )
      (libsource (lib "Integrated_Library_FEDEVEL_APR_2015") (part "C1608X5R0J226M080AC"))
    )
    (comp (ref "C148")
      (value "22u")
      (footprint "C0603")
      (description "CAP CER 22UF 6.3V 20% X5R 0603")
      (fields
        (field (name "MANUFACTURER") "TDK Corporation")
        (field (name "MANUFACTURER PART NUMBER") "C1608X5R0J226M080AC")
        (field (name ".CREATOR") "MM")
        (field (name ".CHECKED PCB") "MM")
        (field (name ".CHECKED SCH") "MM")
      )
      (libsource (lib "Integrated_Library_FEDEVEL_APR_2015") (part "C1608X5R0J226M080AC"))
    )
    (comp (ref "C149")
      (value "220n")
      (footprint "C0201")
      (description "CAP CER 0.22UF 6.3V 20% X5R 0201")
      (fields
        (field (name "MANUFACTURER") "TDK Corporation")
        (field (name "MANUFACTURER PART NUMBER") "C0603X5R0J224M030BB")
        (field (name ".CHECKED PCB") "MM")
        (field (name ".CHECKED SCH") "MM")
        (field (name ".CREATOR") "MM")
      )
      (libsource (lib "Integrated_Library_FEDEVEL_0201") (part "C0603X5R0J224M030BB"))
    )
    (comp (ref "C150")
      (value "220n")
      (footprint "C0201")
      (description "CAP CER 0.22UF 6.3V 20% X5R 0201")
      (fields
        (field (name "MANUFACTURER") "TDK Corporation")
        (field (name "MANUFACTURER PART NUMBER") "C0603X5R0J224M030BB")
        (field (name ".CHECKED PCB") "MM")
        (field (name ".CHECKED SCH") "MM")
        (field (name ".CREATOR") "MM")
      )
      (libsource (lib "Integrated_Library_FEDEVEL_0201") (part "C0603X5R0J224M030BB"))
    )
    (comp (ref "C151")
      (value "22u")
      (footprint "C0603")
      (description "CAP CER 22UF 6.3V 20% X5R 0603")
      (fields
        (field (name "MANUFACTURER") "TDK Corporation")
        (field (name "MANUFACTURER PART NUMBER") "C1608X5R0J226M080AC")
        (field (name ".CREATOR") "MM")
        (field (name ".CHECKED PCB") "MM")
        (field (name ".CHECKED SCH") "MM")
      )
      (libsource (lib "Integrated_Library_FEDEVEL_APR_2015") (part "C1608X5R0J226M080AC"))
    )
    (comp (ref "C152")
      (value "220n")
      (footprint "C0201")
      (description "CAP CER 0.22UF 6.3V 20% X5R 0201")
      (fields
        (field (name "MANUFACTURER") "TDK Corporation")
        (field (name "MANUFACTURER PART NUMBER") "C0603X5R0J224M030BB")
        (field (name ".CHECKED PCB") "MM")
        (field (name ".CHECKED SCH") "MM")
        (field (name ".CREATOR") "MM")
      )
      (libsource (lib "Integrated_Library_FEDEVEL_0201") (part "C0603X5R0J224M030BB"))
    )
    (comp (ref "C153")
      (value "220n")
      (footprint "C0402")
      (description "CAP CER .22UF 25V X5R 20% 0402")
      (fields
        (field (name "MANUFACTURER") "TDK Corporation")
        (field (name "MANUFACTURER PART NUMBER") "C1005X5R1E224M")
      )
      (libsource (lib "Integrated_Library_FEDEVEL_APR_2015") (part "C1005X5R1E224M"))
    )
    (comp (ref "C154")
      (value "220n")
      (footprint "C0201")
      (description "CAP CER 0.22UF 6.3V 20% X5R 0201")
      (fields
        (field (name "MANUFACTURER") "TDK Corporation")
        (field (name "MANUFACTURER PART NUMBER") "C0603X5R0J224M030BB")
        (field (name ".CHECKED PCB") "MM")
        (field (name ".CHECKED SCH") "MM")
        (field (name ".CREATOR") "MM")
      )
      (libsource (lib "Integrated_Library_FEDEVEL_0201") (part "C0603X5R0J224M030BB"))
    )
    (comp (ref "C155")
      (value "220n")
      (footprint "C0201")
      (description "CAP CER 0.22UF 6.3V 20% X5R 0201")
      (fields
        (field (name "MANUFACTURER") "TDK Corporation")
        (field (name "MANUFACTURER PART NUMBER") "C0603X5R0J224M030BB")
        (field (name ".CHECKED PCB") "MM")
        (field (name ".CHECKED SCH") "MM")
        (field (name ".CREATOR") "MM")
      )
      (libsource (lib "Integrated_Library_FEDEVEL_0201") (part "C0603X5R0J224M030BB"))
    )
    (comp (ref "C156")
      (value "22u")
      (footprint "C0603")
      (description "CAP CER 22UF 6.3V 20% X5R 0603")
      (fields
        (field (name "MANUFACTURER") "TDK Corporation")
        (field (name "MANUFACTURER PART NUMBER") "C1608X5R0J226M080AC")
        (field (name ".CREATOR") "MM")
        (field (name ".CHECKED PCB") "MM")
        (field (name ".CHECKED SCH") "MM")
      )
      (libsource (lib "Integrated_Library_FEDEVEL_APR_2015") (part "C1608X5R0J226M080AC"))
    )
    (comp (ref "C157")
      (value "220n")
      (footprint "C0201")
      (description "CAP CER 0.22UF 6.3V 20% X5R 0201")
      (fields
        (field (name "MANUFACTURER") "TDK Corporation")
        (field (name "MANUFACTURER PART NUMBER") "C0603X5R0J224M030BB")
        (field (name ".CHECKED PCB") "MM")
        (field (name ".CHECKED SCH") "MM")
        (field (name ".CREATOR") "MM")
      )
      (libsource (lib "Integrated_Library_FEDEVEL_0201") (part "C0603X5R0J224M030BB"))
    )
    (comp (ref "C158")
      (value "220n")
      (footprint "C0201")
      (description "CAP CER 0.22UF 6.3V 20% X5R 0201")
      (fields
        (field (name "MANUFACTURER") "TDK Corporation")
        (field (name "MANUFACTURER PART NUMBER") "C0603X5R0J224M030BB")
        (field (name ".CHECKED PCB") "MM")
        (field (name ".CHECKED SCH") "MM")
        (field (name ".CREATOR") "MM")
      )
      (libsource (lib "Integrated_Library_FEDEVEL_0201") (part "C0603X5R0J224M030BB"))
    )
    (comp (ref "C159")
      (value "220n")
      (footprint "C0201")
      (description "CAP CER 0.22UF 6.3V 20% X5R 0201")
      (fields
        (field (name "MANUFACTURER") "TDK Corporation")
        (field (name "MANUFACTURER PART NUMBER") "C0603X5R0J224M030BB")
        (field (name ".CHECKED PCB") "MM")
        (field (name ".CHECKED SCH") "MM")
        (field (name ".CREATOR") "MM")
      )
      (libsource (lib "Integrated_Library_FEDEVEL_0201") (part "C0603X5R0J224M030BB"))
    )
    (comp (ref "C160")
      (value "220n")
      (footprint "C0201")
      (description "CAP CER 0.22UF 6.3V 20% X5R 0201")
      (fields
        (field (name "MANUFACTURER") "TDK Corporation")
        (field (name "MANUFACTURER PART NUMBER") "C0603X5R0J224M030BB")
        (field (name ".CHECKED PCB") "MM")
        (field (name ".CHECKED SCH") "MM")
        (field (name ".CREATOR") "MM")
      )
      (libsource (lib "Integrated_Library_FEDEVEL_0201") (part "C0603X5R0J224M030BB"))
    )
    (comp (ref "C161")
      (value "220n")
      (footprint "C0201")
      (description "CAP CER 0.22UF 6.3V 20% X5R 0201")
      (fields
        (field (name "MANUFACTURER") "TDK Corporation")
        (field (name "MANUFACTURER PART NUMBER") "C0603X5R0J224M030BB")
        (field (name ".CHECKED PCB") "MM")
        (field (name ".CHECKED SCH") "MM")
        (field (name ".CREATOR") "MM")
      )
      (libsource (lib "Integrated_Library_FEDEVEL_0201") (part "C0603X5R0J224M030BB"))
    )
    (comp (ref "C162")
      (value "220n")
      (footprint "C0201")
      (description "CAP CER 0.22UF 6.3V 20% X5R 0201")
      (fields
        (field (name "MANUFACTURER") "TDK Corporation")
        (field (name "MANUFACTURER PART NUMBER") "C0603X5R0J224M030BB")
        (field (name ".CHECKED PCB") "MM")
        (field (name ".CHECKED SCH") "MM")
        (field (name ".CREATOR") "MM")
      )
      (libsource (lib "Integrated_Library_FEDEVEL_0201") (part "C0603X5R0J224M030BB"))
    )
    (comp (ref "C163")
      (value "220n")
      (footprint "C0201")
      (description "CAP CER 0.22UF 6.3V 20% X5R 0201")
      (fields
        (field (name "MANUFACTURER") "TDK Corporation")
        (field (name "MANUFACTURER PART NUMBER") "C0603X5R0J224M030BB")
        (field (name ".CHECKED PCB") "MM")
        (field (name ".CHECKED SCH") "MM")
        (field (name ".CREATOR") "MM")
      )
      (libsource (lib "Integrated_Library_FEDEVEL_0201") (part "C0603X5R0J224M030BB"))
    )
    (comp (ref "C164")
      (value "220n")
      (footprint "C0201")
      (description "CAP CER 0.22UF 6.3V 20% X5R 0201")
      (fields
        (field (name "MANUFACTURER") "TDK Corporation")
        (field (name "MANUFACTURER PART NUMBER") "C0603X5R0J224M030BB")
        (field (name ".CHECKED PCB") "MM")
        (field (name ".CHECKED SCH") "MM")
        (field (name ".CREATOR") "MM")
      )
      (libsource (lib "Integrated_Library_FEDEVEL_0201") (part "C0603X5R0J224M030BB"))
    )
    (comp (ref "C165")
      (value "220n")
      (footprint "C0201")
      (description "CAP CER 0.22UF 6.3V 20% X5R 0201")
      (fields
        (field (name "MANUFACTURER") "TDK Corporation")
        (field (name "MANUFACTURER PART NUMBER") "C0603X5R0J224M030BB")
        (field (name ".CHECKED PCB") "MM")
        (field (name ".CHECKED SCH") "MM")
        (field (name ".CREATOR") "MM")
      )
      (libsource (lib "Integrated_Library_FEDEVEL_0201") (part "C0603X5R0J224M030BB"))
    )
    (comp (ref "C166")
      (value "220n")
      (footprint "C0201")
      (description "CAP CER 0.22UF 6.3V 20% X5R 0201")
      (fields
        (field (name "MANUFACTURER") "TDK Corporation")
        (field (name "MANUFACTURER PART NUMBER") "C0603X5R0J224M030BB")
        (field (name ".CHECKED PCB") "MM")
        (field (name ".CHECKED SCH") "MM")
        (field (name ".CREATOR") "MM")
      )
      (libsource (lib "Integrated_Library_FEDEVEL_0201") (part "C0603X5R0J224M030BB"))
    )
    (comp (ref "C167")
      (value "220n")
      (footprint "C0201")
      (description "CAP CER 0.22UF 6.3V 20% X5R 0201")
      (fields
        (field (name "MANUFACTURER") "TDK Corporation")
        (field (name "MANUFACTURER PART NUMBER") "C0603X5R0J224M030BB")
        (field (name ".CHECKED PCB") "MM")
        (field (name ".CHECKED SCH") "MM")
        (field (name ".CREATOR") "MM")
      )
      (libsource (lib "Integrated_Library_FEDEVEL_0201") (part "C0603X5R0J224M030BB"))
    )
    (comp (ref "C168")
      (value "220n")
      (footprint "C0201")
      (description "CAP CER 0.22UF 6.3V 20% X5R 0201")
      (fields
        (field (name "MANUFACTURER") "TDK Corporation")
        (field (name "MANUFACTURER PART NUMBER") "C0603X5R0J224M030BB")
        (field (name ".CHECKED PCB") "MM")
        (field (name ".CHECKED SCH") "MM")
        (field (name ".CREATOR") "MM")
      )
      (libsource (lib "Integrated_Library_FEDEVEL_0201") (part "C0603X5R0J224M030BB"))
    )
    (comp (ref "C169")
      (value "220n")
      (footprint "C0201")
      (description "CAP CER 0.22UF 6.3V 20% X5R 0201")
      (fields
        (field (name "MANUFACTURER") "TDK Corporation")
        (field (name "MANUFACTURER PART NUMBER") "C0603X5R0J224M030BB")
        (field (name ".CHECKED PCB") "MM")
        (field (name ".CHECKED SCH") "MM")
        (field (name ".CREATOR") "MM")
      )
      (libsource (lib "Integrated_Library_FEDEVEL_0201") (part "C0603X5R0J224M030BB"))
    )
    (comp (ref "C170")
      (value "220n")
      (footprint "C0201")
      (description "CAP CER 0.22UF 6.3V 20% X5R 0201")
      (fields
        (field (name "MANUFACTURER") "TDK Corporation")
        (field (name "MANUFACTURER PART NUMBER") "C0603X5R0J224M030BB")
        (field (name ".CHECKED PCB") "MM")
        (field (name ".CHECKED SCH") "MM")
        (field (name ".CREATOR") "MM")
      )
      (libsource (lib "Integrated_Library_FEDEVEL_0201") (part "C0603X5R0J224M030BB"))
    )
    (comp (ref "C171")
      (value "220n")
      (footprint "C0201")
      (description "CAP CER 0.22UF 6.3V 20% X5R 0201")
      (fields
        (field (name "MANUFACTURER") "TDK Corporation")
        (field (name "MANUFACTURER PART NUMBER") "C0603X5R0J224M030BB")
        (field (name ".CHECKED PCB") "MM")
        (field (name ".CHECKED SCH") "MM")
        (field (name ".CREATOR") "MM")
      )
      (libsource (lib "Integrated_Library_FEDEVEL_0201") (part "C0603X5R0J224M030BB"))
    )
    (comp (ref "C172")
      (value "22u")
      (footprint "C0603_small")
      (description "CAP CER 22UF 4V 20% X5R 0603")
      (fields
        (field (name "MANUFACTURER") "Murata Electronics North America")
        (field (name "MANUFACTURER PART NUMBER") "GRM188R60G226MEA0L")
        (field (name ".CHECKED PCB") "MM")
        (field (name ".CHECKED SCH") "RF, used by MM")
        (field (name ".CREATOR") "MM")
      )
      (libsource (lib "Integrated_Library_FEDEVEL_0201") (part "GRM188R60G226MEA0L_small"))
    )
    (comp (ref "C173")
      (value "22u")
      (footprint "C0603_small")
      (description "CAP CER 22UF 4V 20% X5R 0603")
      (fields
        (field (name "MANUFACTURER") "Murata Electronics North America")
        (field (name "MANUFACTURER PART NUMBER") "GRM188R60G226MEA0L")
        (field (name ".CHECKED PCB") "MM")
        (field (name ".CHECKED SCH") "RF, used by MM")
        (field (name ".CREATOR") "MM")
      )
      (libsource (lib "Integrated_Library_FEDEVEL_0201") (part "GRM188R60G226MEA0L_small"))
    )
    (comp (ref "C174")
      (value "220n")
      (footprint "C0201")
      (description "CAP CER 0.22UF 6.3V 20% X5R 0201")
      (fields
        (field (name "MANUFACTURER") "TDK Corporation")
        (field (name "MANUFACTURER PART NUMBER") "C0603X5R0J224M030BB")
        (field (name ".CHECKED PCB") "MM")
        (field (name ".CHECKED SCH") "MM")
        (field (name ".CREATOR") "MM")
      )
      (libsource (lib "Integrated_Library_FEDEVEL_0201") (part "C0603X5R0J224M030BB"))
    )
    (comp (ref "R74")
      (value "0R")
      (footprint "R0402")
      (description "RES 0.0 OHM 1/16W 0402 SMD")
      (fields
        (field (name "MANUFACTURER") "Yageo")
        (field (name "MANUFACTURER PART NUMBER") "RC0402JR-070RL")
      )
      (libsource (lib "Integrated_Library_FEDEVEL_APR_2015") (part "RC0402JR-070RL"))
    )
    (comp (ref "R76")
      (value "0R")
      (footprint "R0402")
      (description "RES 0.0 OHM 1/16W 0402 SMD")
      (fields
        (field (name "MANUFACTURER") "Yageo")
        (field (name "MANUFACTURER PART NUMBER") "RC0402JR-070RL")
      )
      (libsource (lib "Integrated_Library_FEDEVEL_APR_2015") (part "RC0402JR-070RL"))
    )
    (comp (ref "R78")
      (value "0R")
      (footprint "R0402")
      (description "RES 0.0 OHM 1/16W 0402 SMD")
      (fields
        (field (name "MANUFACTURER") "Yageo")
        (field (name "MANUFACTURER PART NUMBER") "RC0402JR-070RL")
      )
      (libsource (lib "Integrated_Library_FEDEVEL_APR_2015") (part "RC0402JR-070RL"))
    )
    (comp (ref "R80")
      (value "0R")
      (footprint "R0402")
      (description "RES 0.0 OHM 1/16W 0402 SMD")
      (fields
        (field (name "MANUFACTURER") "Yageo")
        (field (name "MANUFACTURER PART NUMBER") "RC0402JR-070RL")
      )
      (libsource (lib "Integrated_Library_FEDEVEL_APR_2015") (part "RC0402JR-070RL"))
    )
    (comp (ref "U1")
      (value "MCIMX6Q5EYM10AC_v.ORX")
      (footprint "PBGA624")
      (description "IC MCU 32BIT ARM QUAD 624FCBGA")
      (fields
        (field (name "MANUFACTURER") "Freescale Semiconductor")
        (field (name "MANUFACTURER PART NUMBER") "MCIMX6Q5EYM10AC")
        (field (name ".CREATOR") "MM")
        (field (name ".CHECKED PCB") "MM, checked by RF")
      )
      (libsource (lib "Integrated_Library_FEDEVEL_APR_2015") (part "MCIMX6Q5EYM10AC_v.ORX"))
    )
  )
  (nets
    (net (code "1") (name "+1V1_VDDSOC_CAP") (class "Default")
      (node (ref "C112") (pin "1") (pinfunction "1_1") (pintype "passive"))
      (node (ref "C113") (pin "1") (pinfunction "1_1") (pintype "passive"))
      (node (ref "C114") (pin "1") (pinfunction "1_1") (pintype "passive"))
      (node (ref "C115") (pin "1") (pinfunction "1_1") (pintype "passive"))
      (node (ref "C116") (pin "1") (pinfunction "1_1") (pintype "passive"))
      (node (ref "C117") (pin "1") (pinfunction "1_1") (pintype "passive"))
      (node (ref "C118") (pin "1") (pinfunction "1_1") (pintype "passive"))
      (node (ref "C138") (pin "1") (pinfunction "1_1") (pintype "passive"))
      (node (ref "U1") (pin "N12") (pinfunction "VDD_CACHE_CAP_N12") (pintype "power_in"))
      (node (ref "U1") (pin "R10") (pinfunction "VDDSOC_CAP_1_R10") (pintype "power_in"))
      (node (ref "U1") (pin "T10") (pinfunction "VDDSOC_CAP_2_T10") (pintype "power_in"))
      (node (ref "U1") (pin "T13") (pinfunction "VDDSOC_CAP_3_T13") (pintype "power_in"))
      (node (ref "U1") (pin "T14") (pinfunction "VDDSOC_CAP_4_T14") (pintype "power_in"))
      (node (ref "U1") (pin "U10") (pinfunction "VDDSOC_CAP_5_U10") (pintype "power_in"))
      (node (ref "U1") (pin "U13") (pinfunction "VDDSOC_CAP_6_U13") (pintype "power_in"))
      (node (ref "U1") (pin "U14") (pinfunction "VDDSOC_CAP_7_U14") (pintype "power_in"))
    )
    (net (code "2") (name "+1V2_VDD_ARM_CAP") (class "Default")
      (node (ref "C100") (pin "1") (pinfunction "1_1") (pintype "passive"))
      (node (ref "C101") (pin "1") (pinfunction "1_1") (pintype "passive"))
      (node (ref "C102") (pin "1") (pinfunction "1_1") (pintype "passive"))
      (node (ref "C103") (pin "1") (pinfunction "1_1") (pintype "passive"))
      (node (ref "C104") (pin "1") (pinfunction "1_1") (pintype "passive"))
      (node (ref "C105") (pin "1") (pinfunction "1_1") (pintype "passive"))
      (node (ref "C106") (pin "1") (pinfunction "1_1") (pintype "passive"))
      (node (ref "C97") (pin "1") (pinfunction "1_1") (pintype "passive"))
      (node (ref "C98") (pin "1") (pinfunction "1_1") (pintype "passive"))
      (node (ref "C99") (pin "1") (pinfunction "1_1") (pintype "passive"))
      (node (ref "U1") (pin "H11") (pinfunction "VDDARM23_CAP_1_H11") (pintype "power_in"))
      (node (ref "U1") (pin "H13") (pinfunction "VDDARM_CAP_1_H13") (pintype "power_in"))
      (node (ref "U1") (pin "J11") (pinfunction "VDDARM23_CAP_2_J11") (pintype "power_in"))
      (node (ref "U1") (pin "J13") (pinfunction "VDDARM_CAP_2_J13") (pintype "power_in"))
      (node (ref "U1") (pin "K11") (pinfunction "VDDARM23_CAP_3_K11") (pintype "power_in"))
      (node (ref "U1") (pin "K13") (pinfunction "VDDARM_CAP_3_K13") (pintype "power_in"))
      (node (ref "U1") (pin "L11") (pinfunction "VDDARM23_CAP_4_L11") (pintype "power_in"))
      (node (ref "U1") (pin "L13") (pinfunction "VDDARM_CAP_4_L13") (pintype "power_in"))
      (node (ref "U1") (pin "M11") (pinfunction "VDDARM23_CAP_5_M11") (pintype "power_in"))
      (node (ref "U1") (pin "M13") (pinfunction "VDDARM_CAP_5_M13") (pintype "power_in"))
      (node (ref "U1") (pin "N11") (pinfunction "VDDARM23_CAP_6_N11") (pintype "power_in"))
      (node (ref "U1") (pin "N13") (pinfunction "VDDARM_CAP_6_N13") (pintype "power_in"))
      (node (ref "U1") (pin "P11") (pinfunction "VDDARM23_CAP_7_P11") (pintype "power_in"))
      (node (ref "U1") (pin "P13") (pinfunction "VDDARM_CAP_7_P13") (pintype "power_in"))
      (node (ref "U1") (pin "R11") (pinfunction "VDDARM23_CAP_8_R11") (pintype "power_in"))
      (node (ref "U1") (pin "R13") (pinfunction "VDDARM_CAP_8_R13") (pintype "power_in"))
    )
    (net (code "3") (name "+1V5_DDR") (class "Default")
      (node (ref "C157") (pin "1") (pinfunction "1_1") (pintype "passive"))
      (node (ref "C158") (pin "1") (pinfunction "1_1") (pintype "passive"))
      (node (ref "C159") (pin "1") (pinfunction "1_1") (pintype "passive"))
      (node (ref "C160") (pin "1") (pinfunction "1_1") (pintype "passive"))
      (node (ref "C161") (pin "1") (pinfunction "1_1") (pintype "passive"))
      (node (ref "C162") (pin "1") (pinfunction "1_1") (pintype "passive"))
      (node (ref "C167") (pin "1") (pinfunction "1_1") (pintype "passive"))
      (node (ref "C168") (pin "1") (pinfunction "1_1") (pintype "passive"))
      (node (ref "C169") (pin "1") (pinfunction "1_1") (pintype "passive"))
      (node (ref "C170") (pin "1") (pinfunction "1_1") (pintype "passive"))
      (node (ref "C171") (pin "1") (pinfunction "1_1") (pintype "passive"))
      (node (ref "C172") (pin "1") (pinfunction "1_1") (pintype "passive"))
      (node (ref "C173") (pin "1") (pinfunction "1_1") (pintype "passive"))
    )
    (net (code "4") (name "+1V375_CORE") (class "Default")
      (node (ref "C107") (pin "1") (pinfunction "1_1") (pintype "passive"))
      (node (ref "C108") (pin "1") (pinfunction "1_1") (pintype "passive"))
      (node (ref "C109") (pin "1") (pinfunction "1_1") (pintype "passive"))
      (node (ref "C110") (pin "1") (pinfunction "1_1") (pintype "passive"))
      (node (ref "C111") (pin "1") (pinfunction "1_1") (pintype "passive"))
      (node (ref "C90") (pin "1") (pinfunction "1_1") (pintype "passive"))
      (node (ref "C91") (pin "1") (pinfunction "1_1") (pintype "passive"))
      (node (ref "C92") (pin "1") (pinfunction "1_1") (pintype "passive"))
      (node (ref "C93") (pin "1") (pinfunction "1_1") (pintype "passive"))
      (node (ref "C94") (pin "1") (pinfunction "1_1") (pintype "passive"))
      (node (ref "C95") (pin "1") (pinfunction "1_1") (pintype "passive"))
      (node (ref "C96") (pin "1") (pinfunction "1_1") (pintype "passive"))
      (node (ref "U1") (pin "H14") (pinfunction "VDDARM_IN_1_H14") (pintype "power_in"))
      (node (ref "U1") (pin "J14") (pinfunction "VDDARM_IN_2_J14") (pintype "power_in"))
      (node (ref "U1") (pin "K14") (pinfunction "VDDARM_IN_3_K14") (pintype "power_in"))
      (node (ref "U1") (pin "K9") (pinfunction "VDDARM23_IN_1_K9") (pintype "power_in"))
      (node (ref "U1") (pin "L14") (pinfunction "VDDARM_IN_4_L14") (pintype "power_in"))
      (node (ref "U1") (pin "L9") (pinfunction "VDDARM23_IN_2_L9") (pintype "power_in"))
      (node (ref "U1") (pin "M14") (pinfunction "VDDARM_IN_5_M14") (pintype "power_in"))
      (node (ref "U1") (pin "M9") (pinfunction "VDDARM23_IN_3_M9") (pintype "power_in"))
      (node (ref "U1") (pin "N14") (pinfunction "VDDARM_IN_6_N14") (pintype "power_in"))
      (node (ref "U1") (pin "N9") (pinfunction "VDDARM23_IN_4_N9") (pintype "power_in"))
      (node (ref "U1") (pin "P14") (pinfunction "VDDARM_IN_7_P14") (pintype "power_in"))
      (node (ref "U1") (pin "P9") (pinfunction "VDDARM23_IN_5_P9") (pintype "power_in"))
      (node (ref "U1") (pin "R14") (pinfunction "VDDARM_IN_8_R14") (pintype "power_in"))
      (node (ref "U1") (pin "R9") (pinfunction "VDDARM23_IN_6_R9") (pintype "power_in"))
      (node (ref "U1") (pin "T9") (pinfunction "VDDARM23_IN_7_T9") (pintype "power_in"))
      (node (ref "U1") (pin "U9") (pinfunction "VDDARM23_IN_8_U9") (pintype "power_in"))
    )
    (net (code "5") (name "+1V375_SOC") (class "Default")
      (node (ref "C119") (pin "1") (pinfunction "1_1") (pintype "passive"))
      (node (ref "C120") (pin "1") (pinfunction "1_1") (pintype "passive"))
      (node (ref "C121") (pin "1") (pinfunction "1_1") (pintype "passive"))
      (node (ref "C122") (pin "1") (pinfunction "1_1") (pintype "passive"))
      (node (ref "C123") (pin "1") (pinfunction "1_1") (pintype "passive"))
      (node (ref "C124") (pin "1") (pinfunction "1_1") (pintype "passive"))
      (node (ref "C125") (pin "1") (pinfunction "1_1") (pintype "passive"))
      (node (ref "C126") (pin "1") (pinfunction "1_1") (pintype "passive"))
      (node (ref "C127") (pin "1") (pinfunction "1_1") (pintype "passive"))
      (node (ref "C128") (pin "1") (pinfunction "1_1") (pintype "passive"))
      (node (ref "C129") (pin "1") (pinfunction "1_1") (pintype "passive"))
      (node (ref "U1") (pin "H16") (pinfunction "VDDSOC_IN_1_H16") (pintype "power_in"))
      (node (ref "U1") (pin "J16") (pinfunction "VDDSOC_IN_2_J16") (pintype "power_in"))
      (node (ref "U1") (pin "K16") (pinfunction "VDDSOC_IN_3_K16") (pintype "power_in"))
      (node (ref "U1") (pin "L16") (pinfunction "VDDSOC_IN_4_L16") (pintype "power_in"))
      (node (ref "U1") (pin "M16") (pinfunction "VDDSOC_IN_5_M16") (pintype "power_in"))
      (node (ref "U1") (pin "N16") (pinfunction "VDDSOC_IN_6_N16") (pintype "power_in"))
      (node (ref "U1") (pin "P16") (pinfunction "VDDSOC_IN_7_P16") (pintype "power_in"))
      (node (ref "U1") (pin "R16") (pinfunction "VDDSOC_IN_8_R16") (pintype "power_in"))
      (node (ref "U1") (pin "T16") (pinfunction "VDDSOC_IN_9_T16") (pintype "power_in"))
      (node (ref "U1") (pin "U16") (pinfunction "VDDSOC_IN_10_U16") (pintype "power_in"))
    )
    (net (code "6") (name "+2V5") (class "Default")
      (node (ref "C153") (pin "1") (pinfunction "1_1") (pintype "passive"))
      (node (ref "R74") (pin "2") (pinfunction "2_2") (pintype "passive"))
      (node (ref "R78") (pin "2") (pinfunction "2_2") (pintype "passive"))
      (node (ref "R80") (pin "2") (pinfunction "2_2") (pintype "passive"))
    )
    (net (code "7") (name "+3V0_ALWAYS") (class "Default")
      (node (ref "C136") (pin "1") (pinfunction "1_1") (pintype "passive"))
      (node (ref "C137") (pin "1") (pinfunction "1_1") (pintype "passive"))
      (node (ref "C142") (pin "1") (pinfunction "1_1") (pintype "passive"))
      (node (ref "U1") (pin "G11") (pinfunction "VDD_SNVS_IN_G11") (pintype "power_in"))
      (node (ref "U1") (pin "H9") (pinfunction "VDDHIGH_IN_1_H9") (pintype "power_in"))
      (node (ref "U1") (pin "J9") (pinfunction "VDDHIGH_IN_2_J9") (pintype "power_in"))
    )
    (net (code "8") (name "+3V3") (class "Default")
      (node (ref "C144") (pin "1") (pinfunction "1_1") (pintype "passive"))
      (node (ref "C146") (pin "1") (pinfunction "1_1") (pintype "passive"))
      (node (ref "C147") (pin "1") (pinfunction "1_1") (pintype "passive"))
      (node (ref "C148") (pin "1") (pinfunction "1_1") (pintype "passive"))
      (node (ref "C154") (pin "1") (pinfunction "1_1") (pintype "passive"))
      (node (ref "C163") (pin "1") (pinfunction "1_1") (pintype "passive"))
      (node (ref "C164") (pin "1") (pinfunction "1_1") (pintype "passive"))
      (node (ref "C165") (pin "1") (pinfunction "1_1") (pintype "passive"))
      (node (ref "C166") (pin "1") (pinfunction "1_1") (pintype "passive"))
      (node (ref "C174") (pin "1") (pinfunction "1_1") (pintype "passive"))
      (node (ref "R76") (pin "2") (pinfunction "2_2") (pintype "passive"))
      (node (ref "U1") (pin "G14") (pinfunction "NVCC_SD3_G14") (pintype "power_in"))
      (node (ref "U1") (pin "G15") (pinfunction "NVCC_NANDF_G15") (pintype "power_in"))
      (node (ref "U1") (pin "G16") (pinfunction "NVCC_SD1_G16") (pintype "power_in"))
      (node (ref "U1") (pin "G17") (pinfunction "NVCC_SD2_G17") (pintype "power_in"))
      (node (ref "U1") (pin "J7") (pinfunction "NVCC_JTAG_J7") (pintype "power_in"))
      (node (ref "U1") (pin "K19") (pinfunction "NVCC_EIM0_K19") (pintype "power_in"))
      (node (ref "U1") (pin "L19") (pinfunction "NVCC_EIM1_L19") (pintype "power_in"))
      (node (ref "U1") (pin "M19") (pinfunction "NVCC_EIM2_M19") (pintype "power_in"))
      (node (ref "U1") (pin "P19") (pinfunction "NVCC_LCD_P19") (pintype "power_in"))
      (node (ref "U1") (pin "P7") (pinfunction "NVCC_GPIO_P7") (pintype "power_in"))
    )
    (net (code "9") (name "/+1V1_NVCC_PLL_OUT") (class "Default")
      (node (ref "C150") (pin "1") (pinfunction "1_1") (pintype "passive"))
      (node (ref "C151") (pin "1") (pinfunction "1_1") (pintype "passive"))
      (node (ref "U1") (pin "E8") (pinfunction "NVCC_PLL_OUT_E8") (pintype "power_in"))
    )
    (net (code "10") (name "/+2V5_VDDHIGH_VPH") (class "Default")
      (node (ref "C139") (pin "1") (pinfunction "1_1") (pintype "passive"))
      (node (ref "C140") (pin "1") (pinfunction "1_1") (pintype "passive"))
      (node (ref "C141") (pin "1") (pinfunction "1_1") (pintype "passive"))
      (node (ref "U1") (pin "H10") (pinfunction "VDDHIGH_CAP_1_H10") (pintype "power_in"))
      (node (ref "U1") (pin "J10") (pinfunction "VDDHIGH_CAP_2_J10") (pintype "power_in"))
    )
    (net (code "11") (name "/+NVCC_CSI") (class "Default")
      (node (ref "C145") (pin "1") (pinfunction "1_1") (pintype "passive"))
      (node (ref "R76") (pin "1") (pinfunction "1_1") (pintype "passive"))
      (node (ref "U1") (pin "N7") (pinfunction "NVCC_CSI_N7") (pintype "power_in"))
    )
    (net (code "12") (name "/+NVCC_ENET") (class "Default")
      (node (ref "C155") (pin "1") (pinfunction "1_1") (pintype "passive"))
      (node (ref "C156") (pin "1") (pinfunction "1_1") (pintype "passive"))
      (node (ref "R74") (pin "1") (pinfunction "1_1") (pintype "passive"))
      (node (ref "U1") (pin "R19") (pinfunction "NVCC_ENET_R19") (pintype "power_in"))
    )
    (net (code "13") (name "/+NVCC_MIPI") (class "Default")
      (node (ref "C149") (pin "1") (pinfunction "1_1") (pintype "passive"))
      (node (ref "R78") (pin "1") (pinfunction "1_1") (pintype "passive"))
      (node (ref "U1") (pin "K7") (pinfunction "NVCC_MIPI_K7") (pintype "power_in"))
    )
    (net (code "14") (name "/+NVCC_RGMII") (class "Default")
      (node (ref "C152") (pin "1") (pinfunction "1_1") (pintype "passive"))
      (node (ref "R80") (pin "1") (pinfunction "1_1") (pintype "passive"))
      (node (ref "U1") (pin "G18") (pinfunction "NVCC_RGMII_G18") (pintype "power_in"))
    )
    (net (code "15") (name "/+VDDPU") (class "Default")
      (node (ref "C130") (pin "1") (pinfunction "1_1") (pintype "passive"))
      (node (ref "C131") (pin "1") (pinfunction "1_1") (pintype "passive"))
      (node (ref "C132") (pin "1") (pinfunction "1_1") (pintype "passive"))
      (node (ref "C133") (pin "1") (pinfunction "1_1") (pintype "passive"))
      (node (ref "C134") (pin "1") (pinfunction "1_1") (pintype "passive"))
      (node (ref "C135") (pin "1") (pinfunction "1_1") (pintype "passive"))
      (node (ref "U1") (pin "H17") (pinfunction "VDDPU_CAP_1_H17") (pintype "power_in"))
      (node (ref "U1") (pin "J17") (pinfunction "VDDPU_CAP_2_J17") (pintype "power_in"))
      (node (ref "U1") (pin "K17") (pinfunction "VDDPU_CAP_3_K17") (pintype "power_in"))
      (node (ref "U1") (pin "L17") (pinfunction "VDDPU_CAP_4_L17") (pintype "power_in"))
      (node (ref "U1") (pin "M17") (pinfunction "VDDPU_CAP_5_M17") (pintype "power_in"))
      (node (ref "U1") (pin "N17") (pinfunction "VDDPU_CAP_6_N17") (pintype "power_in"))
      (node (ref "U1") (pin "P17") (pinfunction "VDDPU_CAP_7_P17") (pintype "power_in"))
    )
    (net (code "16") (name "/+VDD_SNVS_CAP") (class "Default")
      (node (ref "C143") (pin "1") (pinfunction "1_1") (pintype "passive"))
      (node (ref "U1") (pin "G9") (pinfunction "VDD_SNVS_CAP_G9") (pintype "power_in"))
    )
    (net (code "17") (name "GND") (class "Default")
      (node (ref "C100") (pin "2") (pinfunction "2_2") (pintype "passive"))
      (node (ref "C101") (pin "2") (pinfunction "2_2") (pintype "passive"))
      (node (ref "C102") (pin "2") (pinfunction "2_2") (pintype "passive"))
      (node (ref "C103") (pin "2") (pinfunction "2_2") (pintype "passive"))
      (node (ref "C104") (pin "2") (pinfunction "2_2") (pintype "passive"))
      (node (ref "C105") (pin "2") (pinfunction "2_2") (pintype "passive"))
      (node (ref "C106") (pin "2") (pinfunction "2_2") (pintype "passive"))
      (node (ref "C107") (pin "2") (pinfunction "2_2") (pintype "passive"))
      (node (ref "C108") (pin "2") (pinfunction "2_2") (pintype "passive"))
      (node (ref "C109") (pin "2") (pinfunction "2_2") (pintype "passive"))
      (node (ref "C110") (pin "2") (pinfunction "2_2") (pintype "passive"))
      (node (ref "C111") (pin "2") (pinfunction "2_2") (pintype "passive"))
      (node (ref "C112") (pin "2") (pinfunction "2_2") (pintype "passive"))
      (node (ref "C113") (pin "2") (pinfunction "2_2") (pintype "passive"))
      (node (ref "C114") (pin "2") (pinfunction "2_2") (pintype "passive"))
      (node (ref "C115") (pin "2") (pinfunction "2_2") (pintype "passive"))
      (node (ref "C116") (pin "2") (pinfunction "2_2") (pintype "passive"))
      (node (ref "C117") (pin "2") (pinfunction "2_2") (pintype "passive"))
      (node (ref "C118") (pin "2") (pinfunction "2_2") (pintype "passive"))
      (node (ref "C119") (pin "2") (pinfunction "2_2") (pintype "passive"))
      (node (ref "C120") (pin "2") (pinfunction "2_2") (pintype "passive"))
      (node (ref "C121") (pin "2") (pinfunction "2_2") (pintype "passive"))
      (node (ref "C122") (pin "2") (pinfunction "2_2") (pintype "passive"))
      (node (ref "C123") (pin "2") (pinfunction "2_2") (pintype "passive"))
      (node (ref "C124") (pin "2") (pinfunction "2_2") (pintype "passive"))
      (node (ref "C125") (pin "2") (pinfunction "2_2") (pintype "passive"))
      (node (ref "C126") (pin "2") (pinfunction "2_2") (pintype "passive"))
      (node (ref "C127") (pin "2") (pinfunction "2_2") (pintype "passive"))
      (node (ref "C128") (pin "2") (pinfunction "2_2") (pintype "passive"))
      (node (ref "C129") (pin "2") (pinfunction "2_2") (pintype "passive"))
      (node (ref "C130") (pin "2") (pinfunction "2_2") (pintype "passive"))
      (node (ref "C131") (pin "2") (pinfunction "2_2") (pintype "passive"))
      (node (ref "C132") (pin "2") (pinfunction "2_2") (pintype "passive"))
      (node (ref "C133") (pin "2") (pinfunction "2_2") (pintype "passive"))
      (node (ref "C134") (pin "2") (pinfunction "2_2") (pintype "passive"))
      (node (ref "C135") (pin "2") (pinfunction "2_2") (pintype "passive"))
      (node (ref "C136") (pin "2") (pinfunction "2_2") (pintype "passive"))
      (node (ref "C137") (pin "2") (pinfunction "2_2") (pintype "passive"))
      (node (ref "C138") (pin "2") (pinfunction "2_2") (pintype "passive"))
      (node (ref "C139") (pin "2") (pinfunction "2_2") (pintype "passive"))
      (node (ref "C140") (pin "2") (pinfunction "2_2") (pintype "passive"))
      (node (ref "C141") (pin "2") (pinfunction "2_2") (pintype "passive"))
      (node (ref "C142") (pin "2") (pinfunction "2_2") (pintype "passive"))
      (node (ref "C143") (pin "2") (pinfunction "2_2") (pintype "passive"))
      (node (ref "C144") (pin "2") (pinfunction "2_2") (pintype "passive"))
      (node (ref "C145") (pin "2") (pinfunction "2_2") (pintype "passive"))
      (node (ref "C146") (pin "2") (pinfunction "2_2") (pintype "passive"))
      (node (ref "C147") (pin "2") (pinfunction "2_2") (pintype "passive"))
      (node (ref "C148") (pin "2") (pinfunction "2_2") (pintype "passive"))
      (node (ref "C149") (pin "2") (pinfunction "2_2") (pintype "passive"))
      (node (ref "C150") (pin "2") (pinfunction "2_2") (pintype "passive"))
      (node (ref "C151") (pin "2") (pinfunction "2_2") (pintype "passive"))
      (node (ref "C152") (pin "2") (pinfunction "2_2") (pintype "passive"))
      (node (ref "C153") (pin "2") (pinfunction "2_2") (pintype "passive"))
      (node (ref "C154") (pin "2") (pinfunction "2_2") (pintype "passive"))
      (node (ref "C155") (pin "2") (pinfunction "2_2") (pintype "passive"))
      (node (ref "C156") (pin "2") (pinfunction "2_2") (pintype "passive"))
      (node (ref "C157") (pin "2") (pinfunction "2_2") (pintype "passive"))
      (node (ref "C158") (pin "2") (pinfunction "2_2") (pintype "passive"))
      (node (ref "C159") (pin "2") (pinfunction "2_2") (pintype "passive"))
      (node (ref "C160") (pin "2") (pinfunction "2_2") (pintype "passive"))
      (node (ref "C161") (pin "2") (pinfunction "2_2") (pintype "passive"))
      (node (ref "C162") (pin "2") (pinfunction "2_2") (pintype "passive"))
      (node (ref "C163") (pin "2") (pinfunction "2_2") (pintype "passive"))
      (node (ref "C164") (pin "2") (pinfunction "2_2") (pintype "passive"))
      (node (ref "C165") (pin "2") (pinfunction "2_2") (pintype "passive"))
      (node (ref "C166") (pin "2") (pinfunction "2_2") (pintype "passive"))
      (node (ref "C167") (pin "2") (pinfunction "2_2") (pintype "passive"))
      (node (ref "C168") (pin "2") (pinfunction "2_2") (pintype "passive"))
      (node (ref "C169") (pin "2") (pinfunction "2_2") (pintype "passive"))
      (node (ref "C170") (pin "2") (pinfunction "2_2") (pintype "passive"))
      (node (ref "C171") (pin "2") (pinfunction "2_2") (pintype "passive"))
      (node (ref "C172") (pin "2") (pinfunction "2_2") (pintype "passive"))
      (node (ref "C173") (pin "2") (pinfunction "2_2") (pintype "passive"))
      (node (ref "C174") (pin "2") (pinfunction "2_2") (pintype "passive"))
      (node (ref "C90") (pin "2") (pinfunction "2_2") (pintype "passive"))
      (node (ref "C91") (pin "2") (pinfunction "2_2") (pintype "passive"))
      (node (ref "C92") (pin "2") (pinfunction "2_2") (pintype "passive"))
      (node (ref "C93") (pin "2") (pinfunction "2_2") (pintype "passive"))
      (node (ref "C94") (pin "2") (pinfunction "2_2") (pintype "passive"))
      (node (ref "C95") (pin "2") (pinfunction "2_2") (pintype "passive"))
      (node (ref "C96") (pin "2") (pinfunction "2_2") (pintype "passive"))
      (node (ref "C97") (pin "2") (pinfunction "2_2") (pintype "passive"))
      (node (ref "C98") (pin "2") (pinfunction "2_2") (pintype "passive"))
      (node (ref "C99") (pin "2") (pinfunction "2_2") (pintype "passive"))
      (node (ref "U1") (pin "A13") (pinfunction "GND_1_A13") (pintype "power_in"))
      (node (ref "U1") (pin "A25") (pinfunction "GND_2_A25") (pintype "power_in"))
      (node (ref "U1") (pin "A4") (pinfunction "GND_3_A4") (pintype "power_in"))
      (node (ref "U1") (pin "A5") (pinfunction "FA_ANA_A5") (pintype "power_in"))
      (node (ref "U1") (pin "A8") (pinfunction "GND_4_A8") (pintype "power_in"))
      (node (ref "U1") (pin "AA10") (pinfunction "GND_5_AA10") (pintype "power_in"))
      (node (ref "U1") (pin "AA13") (pinfunction "GND_6_AA13") (pintype "power_in"))
      (node (ref "U1") (pin "AA16") (pinfunction "GND_7_AA16") (pintype "power_in"))
      (node (ref "U1") (pin "AA19") (pinfunction "GND_8_AA19") (pintype "power_in"))
      (node (ref "U1") (pin "AA22") (pinfunction "GND_9_AA22") (pintype "power_in"))
      (node (ref "U1") (pin "AA7") (pinfunction "GND_10_AA7") (pintype "power_in"))
      (node (ref "U1") (pin "AB24") (pinfunction "GND_11_AB24") (pintype "power_in"))
      (node (ref "U1") (pin "AB3") (pinfunction "GND_12_AB3") (pintype "power_in"))
      (node (ref "U1") (pin "AD10") (pinfunction "GND_13_AD10") (pintype "power_in"))
      (node (ref "U1") (pin "AD13") (pinfunction "GND_14_AD13") (pintype "power_in"))
      (node (ref "U1") (pin "AD16") (pinfunction "GND_15_AD16") (pintype "power_in"))
      (node (ref "U1") (pin "AD19") (pinfunction "GND_16_AD19") (pintype "power_in"))
      (node (ref "U1") (pin "AD22") (pinfunction "GND_17_AD22") (pintype "power_in"))
      (node (ref "U1") (pin "AD4") (pinfunction "GND_18_AD4") (pintype "power_in"))
      (node (ref "U1") (pin "AD7") (pinfunction "GND_19_AD7") (pintype "power_in"))
      (node (ref "U1") (pin "AE1") (pinfunction "GND_20_AE1") (pintype "power_in"))
      (node (ref "U1") (pin "AE25") (pinfunction "GND_21_AE25") (pintype "power_in"))
      (node (ref "U1") (pin "B4") (pinfunction "GND_22_B4") (pintype "power_in"))
      (node (ref "U1") (pin "B5") (pinfunction "VDD_FA_B5") (pintype "power_in"))
      (node (ref "U1") (pin "C1") (pinfunction "GND_23_C1") (pintype "power_in"))
      (node (ref "U1") (pin "C10") (pinfunction "GND_24_C10") (pintype "power_in"))
      (node (ref "U1") (pin "C4") (pinfunction "GND_25_C4") (pintype "power_in"))
      (node (ref "U1") (pin "C6") (pinfunction "GND_26_C6") (pintype "power_in"))
      (node (ref "U1") (pin "D3") (pinfunction "GND_27_D3") (pintype "power_in"))
      (node (ref "U1") (pin "D6") (pinfunction "GND_28_D6") (pintype "power_in"))
      (node (ref "U1") (pin "D8") (pinfunction "GND_29_D8") (pintype "power_in"))
      (node (ref "U1") (pin "E5") (pinfunction "GND_30_E5") (pintype "power_in"))
      (node (ref "U1") (pin "E6") (pinfunction "GND_31_E6") (pintype "power_in"))
      (node (ref "U1") (pin "E7") (pinfunction "GND_32_E7") (pintype "power_in"))
      (node (ref "U1") (pin "F5") (pinfunction "GND_33_F5") (pintype "power_in"))
      (node (ref "U1") (pin "F6") (pinfunction "GND_34_F6") (pintype "power_in"))
      (node (ref "U1") (pin "F7") (pinfunction "GND_35_F7") (pintype "power_in"))
      (node (ref "U1") (pin "F8") (pinfunction "GND_36_F8") (pintype "power_in"))
      (node (ref "U1") (pin "G10") (pinfunction "GND_37_G10") (pintype "power_in"))
      (node (ref "U1") (pin "G19") (pinfunction "GND_38_G19") (pintype "power_in"))
      (node (ref "U1") (pin "G3") (pinfunction "GND_39_G3") (pintype "power_in"))
      (node (ref "U1") (pin "H12") (pinfunction "GND_40_H12") (pintype "power_in"))
      (node (ref "U1") (pin "H15") (pinfunction "GND_41_H15") (pintype "power_in"))
      (node (ref "U1") (pin "H18") (pinfunction "GND_42_H18") (pintype "power_in"))
      (node (ref "U1") (pin "H8") (pinfunction "GND_43_H8") (pintype "power_in"))
      (node (ref "U1") (pin "J12") (pinfunction "GND_44_J12") (pintype "power_in"))
      (node (ref "U1") (pin "J15") (pinfunction "GND_45_J15") (pintype "power_in"))
      (node (ref "U1") (pin "J18") (pinfunction "GND_46_J18") (pintype "power_in"))
      (node (ref "U1") (pin "J2") (pinfunction "GND_47_J2") (pintype "power_in"))
      (node (ref "U1") (pin "J8") (pinfunction "GND_48_J8") (pintype "power_in"))
      (node (ref "U1") (pin "K10") (pinfunction "GND_49_K10") (pintype "power_in"))
      (node (ref "U1") (pin "K12") (pinfunction "GND_50_K12") (pintype "power_in"))
      (node (ref "U1") (pin "K15") (pinfunction "GND_51_K15") (pintype "power_in"))
      (node (ref "U1") (pin "K18") (pinfunction "GND_52_K18") (pintype "power_in"))
      (node (ref "U1") (pin "K8") (pinfunction "GND_53_K8") (pintype "power_in"))
      (node (ref "U1") (pin "L10") (pinfunction "GND_54_L10") (pintype "power_in"))
      (node (ref "U1") (pin "L12") (pinfunction "GND_55_L12") (pintype "power_in"))
      (node (ref "U1") (pin "L15") (pinfunction "GND_56_L15") (pintype "power_in"))
      (node (ref "U1") (pin "L18") (pinfunction "GND_57_L18") (pintype "power_in"))
      (node (ref "U1") (pin "L2") (pinfunction "GND_58_L2") (pintype "power_in"))
      (node (ref "U1") (pin "L5") (pinfunction "GND_59_L5") (pintype "power_in"))
      (node (ref "U1") (pin "L8") (pinfunction "GND_60_L8") (pintype "power_in"))
      (node (ref "U1") (pin "M10") (pinfunction "GND_61_M10") (pintype "power_in"))
      (node (ref "U1") (pin "M12") (pinfunction "GND_62_M12") (pintype "power_in"))
      (node (ref "U1") (pin "M15") (pinfunction "GND_63_M15") (pintype "power_in"))
      (node (ref "U1") (pin "M18") (pinfunction "GND_64_M18") (pintype "power_in"))
      (node (ref "U1") (pin "M8") (pinfunction "GND_65_M8") (pintype "power_in"))
      (node (ref "U1") (pin "N10") (pinfunction "GND_66_N10") (pintype "power_in"))
      (node (ref "U1") (pin "N15") (pinfunction "GND_67_N15") (pintype "power_in"))
      (node (ref "U1") (pin "N18") (pinfunction "GND_68_N18") (pintype "power_in"))
      (node (ref "U1") (pin "N8") (pinfunction "GND_69_N8") (pintype "power_in"))
      (node (ref "U1") (pin "P10") (pinfunction "GND_70_P10") (pintype "power_in"))
      (node (ref "U1") (pin "P12") (pinfunction "GND_71_P12") (pintype "power_in"))
      (node (ref "U1") (pin "P15") (pinfunction "GND_72_P15") (pintype "power_in"))
      (node (ref "U1") (pin "P18") (pinfunction "GND_73_P18") (pintype "power_in"))
      (node (ref "U1") (pin "P8") (pinfunction "GND_74_P8") (pintype "power_in"))
      (node (ref "U1") (pin "R12") (pinfunction "GND_75_R12") (pintype "power_in"))
      (node (ref "U1") (pin "R15") (pinfunction "GND_76_R15") (pintype "power_in"))
      (node (ref "U1") (pin "R17") (pinfunction "GND_77_R17") (pintype "power_in"))
      (node (ref "U1") (pin "R8") (pinfunction "GND_78_R8") (pintype "power_in"))
      (node (ref "U1") (pin "T11") (pinfunction "GND_79_T11") (pintype "power_in"))
      (node (ref "U1") (pin "T12") (pinfunction "GND_80_T12") (pintype "power_in"))
      (node (ref "U1") (pin "T15") (pinfunction "GND_81_T15") (pintype "power_in"))
      (node (ref "U1") (pin "T17") (pinfunction "GND_82_T17") (pintype "power_in"))
      (node (ref "U1") (pin "T19") (pinfunction "GND_83_T19") (pintype "power_in"))
      (node (ref "U1") (pin "T8") (pinfunction "GND_84_T8") (pintype "power_in"))
      (node (ref "U1") (pin "U11") (pinfunction "GND_85_U11") (pintype "power_in"))
      (node (ref "U1") (pin "U12") (pinfunction "GND_86_U12") (pintype "power_in"))
      (node (ref "U1") (pin "U15") (pinfunction "GND_87_U15") (pintype "power_in"))
      (node (ref "U1") (pin "U17") (pinfunction "GND_88_U17") (pintype "power_in"))
      (node (ref "U1") (pin "U19") (pinfunction "GND_90_U19") (pintype "power_in"))
      (node (ref "U1") (pin "U8") (pinfunction "GND_89_U8") (pintype "power_in"))
      (node (ref "U1") (pin "V19") (pinfunction "GND_92_V19") (pintype "power_in"))
      (node (ref "U1") (pin "V8") (pinfunction "GND_91_V8") (pintype "power_in"))
      (node (ref "U1") (pin "W10") (pinfunction "GND_97_W10") (pintype "power_in"))
      (node (ref "U1") (pin "W11") (pinfunction "GND_98_W11") (pintype "power_in"))
      (node (ref "U1") (pin "W12") (pinfunction "GND_99_W12") (pintype "power_in"))
      (node (ref "U1") (pin "W13") (pinfunction "GND_100_W13") (pintype "power_in"))
      (node (ref "U1") (pin "W15") (pinfunction "GND_101_W15") (pintype "power_in"))
      (node (ref "U1") (pin "W16") (pinfunction "GND_102_W16") (pintype "power_in"))
      (node (ref "U1") (pin "W17") (pinfunction "GND_103_W17") (pintype "power_in"))
      (node (ref "U1") (pin "W18") (pinfunction "GND_104_W18") (pintype "power_in"))
      (node (ref "U1") (pin "W19") (pinfunction "GND_105_W19") (pintype "power_in"))
      (node (ref "U1") (pin "W3") (pinfunction "GND_93_W3") (pintype "power_in"))
      (node (ref "U1") (pin "W7") (pinfunction "GND_94_W7") (pintype "power_in"))
      (node (ref "U1") (pin "W8") (pinfunction "GND_95_W8") (pintype "power_in"))
      (node (ref "U1") (pin "W9") (pinfunction "GND_96_W9") (pintype "power_in"))
      (node (ref "U1") (pin "Y24") (pinfunction "GND_107_Y24") (pintype "power_in"))
      (node (ref "U1") (pin "Y5") (pinfunction "GND_106_Y5") (pintype "power_in"))
    )
    (net (code "18") (name "unconnected-(U1B-GPANAIO-PadC8)") (class "Default")
      (node (ref "U1") (pin "C8") (pinfunction "GPANAIO_C8") (pintype "power_in+no_connect"))
    )
  )
)
